# display_driver_shift_reg.net
KiCad netlist of a schematic drawn in EAGLE
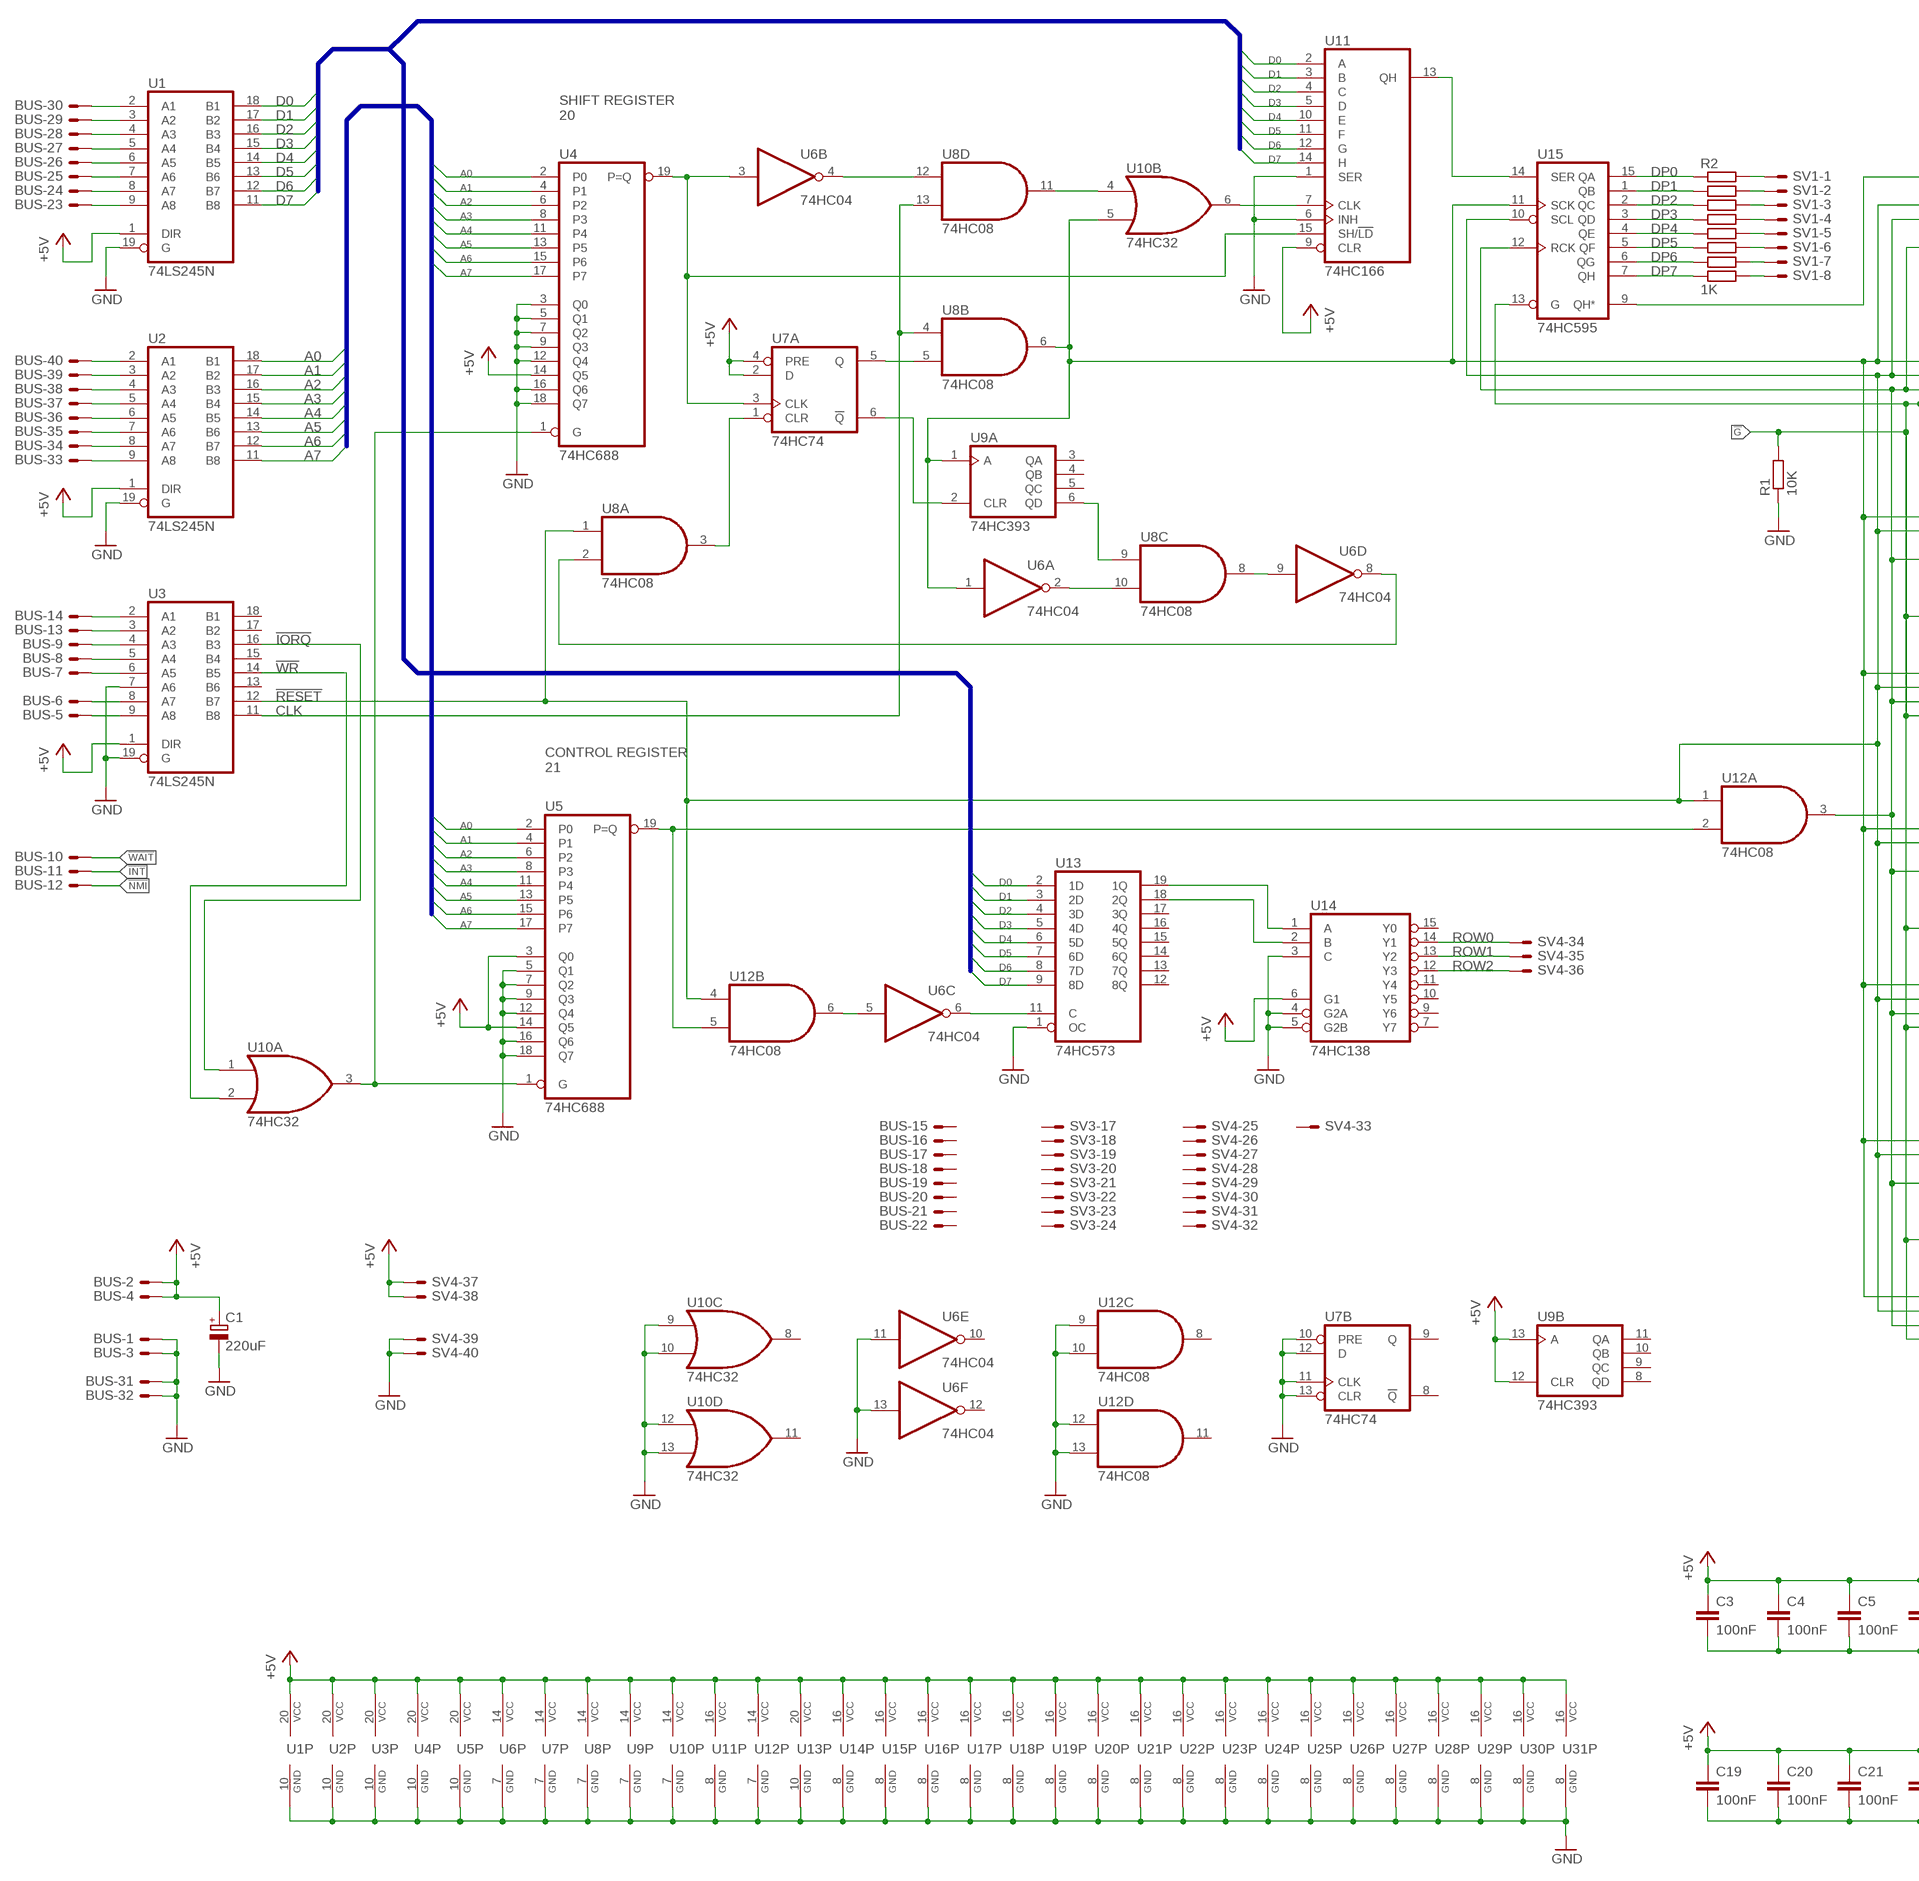
[diagram p0: schematic, sheet 1, part 1 of 2]
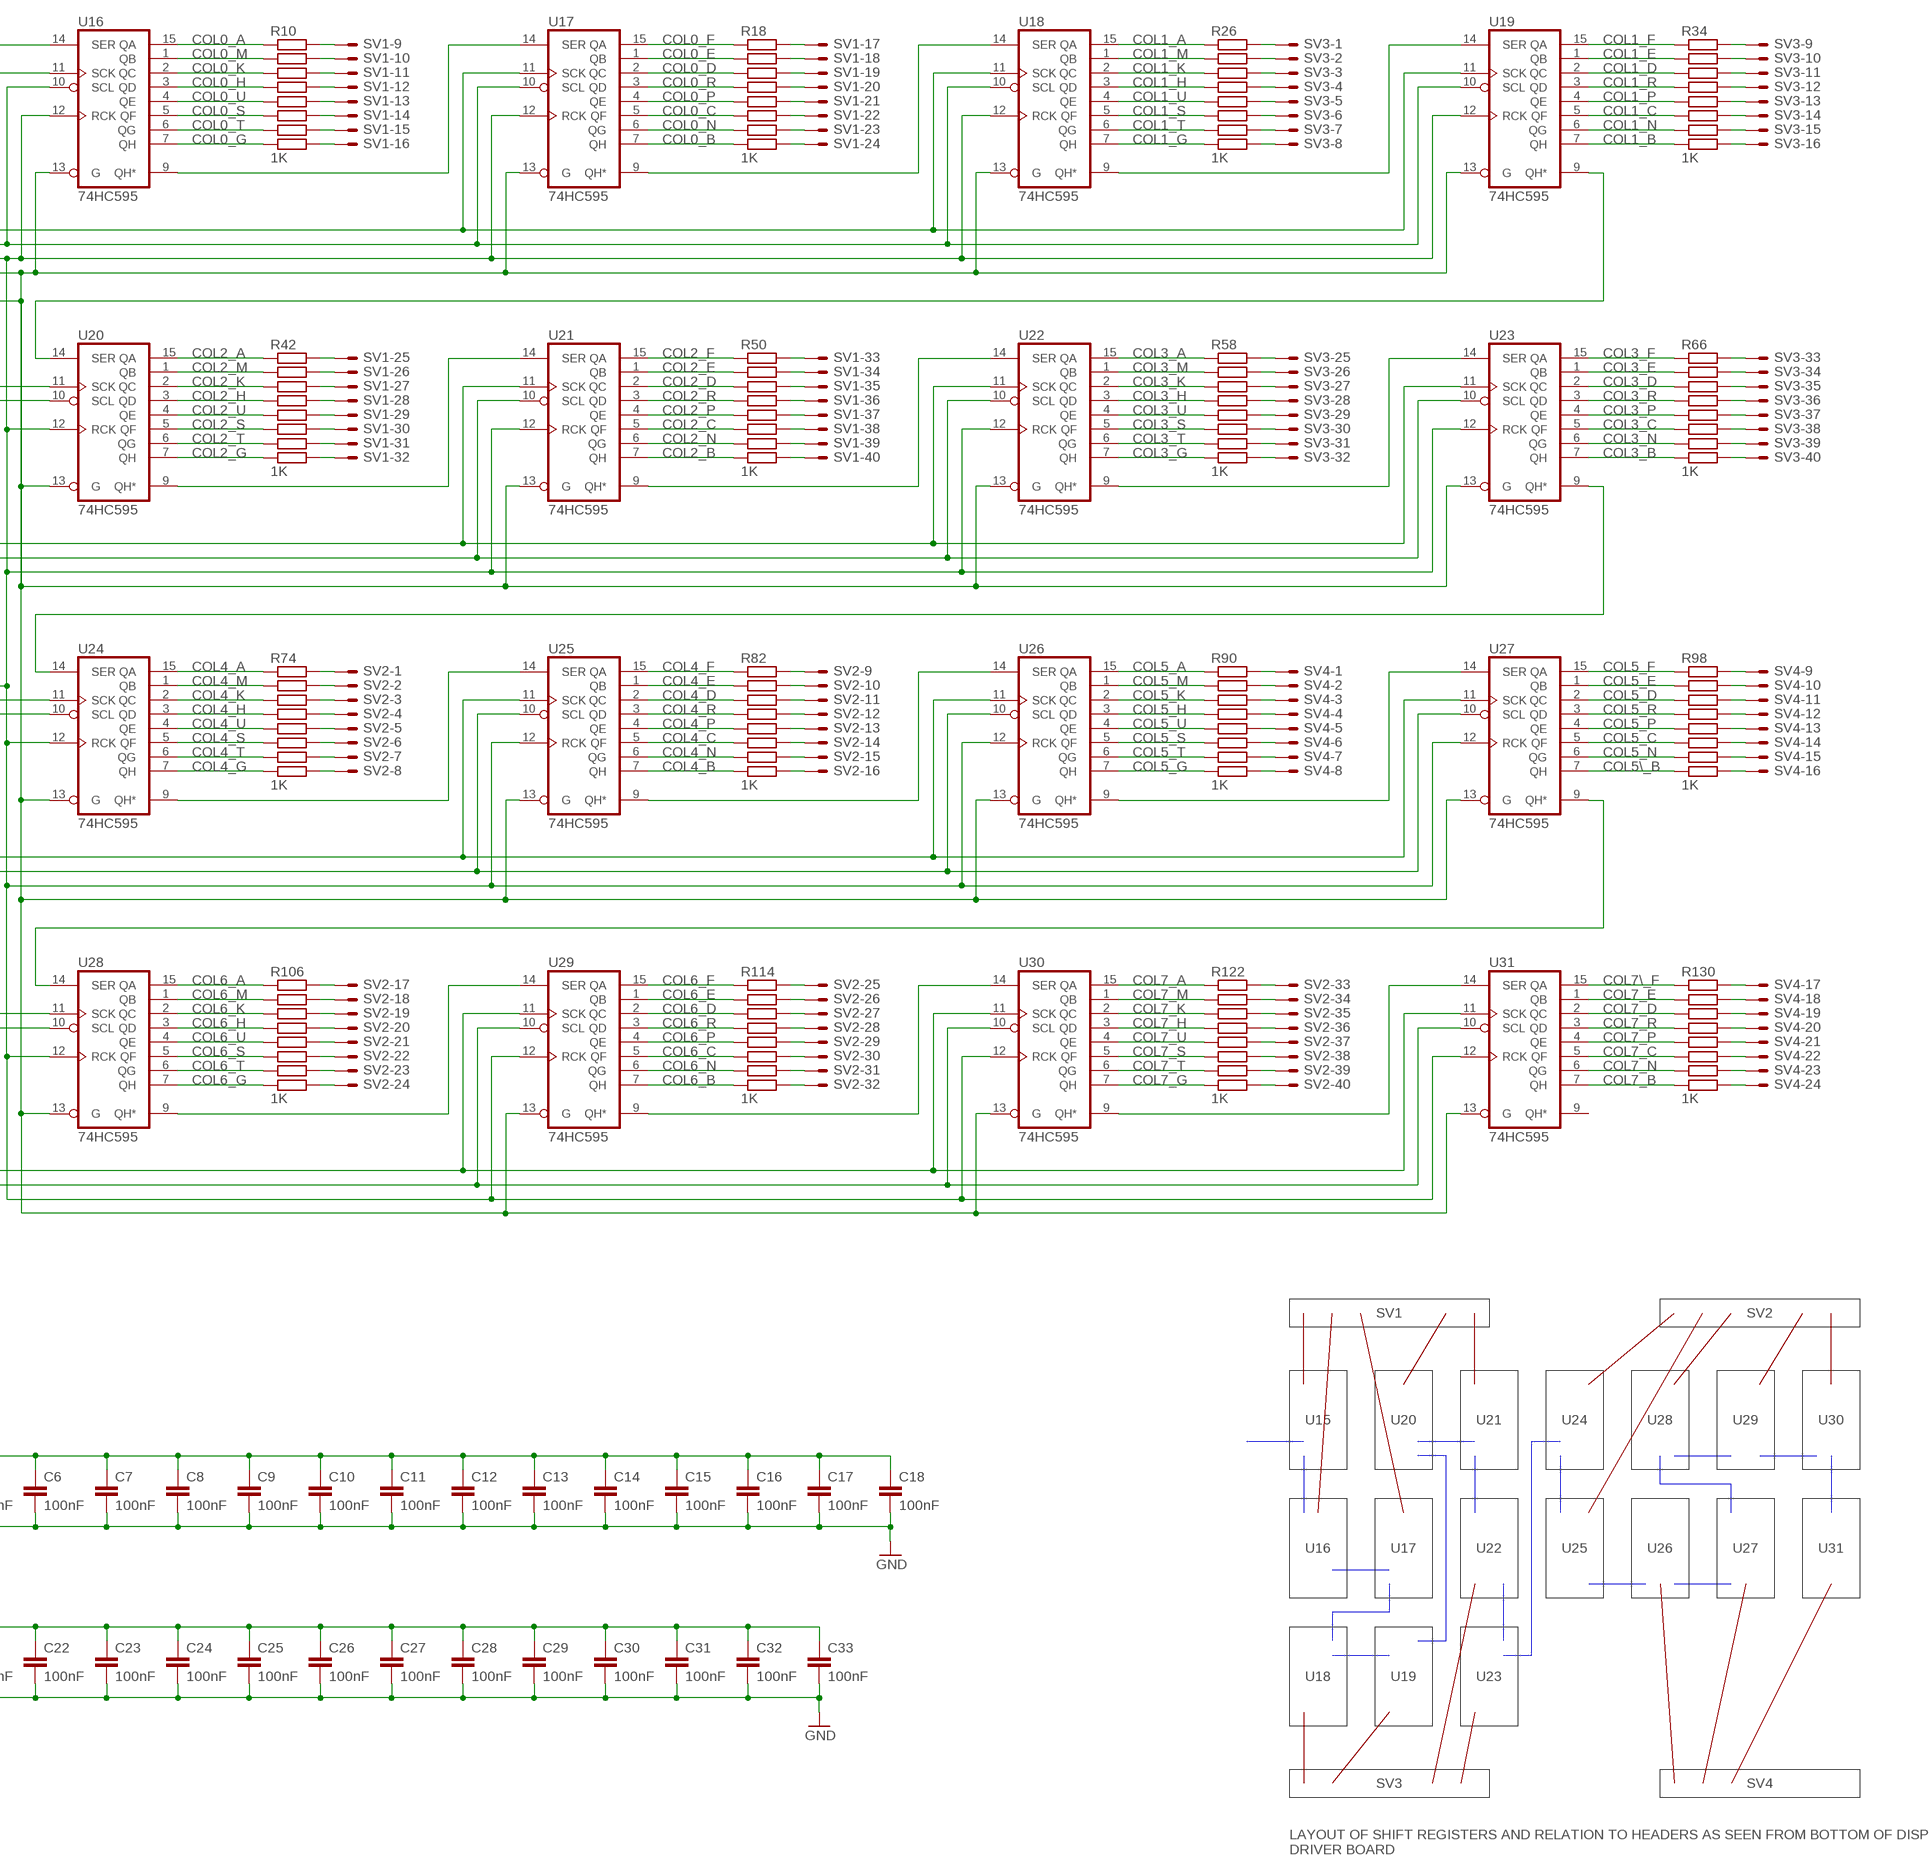
[diagram p1: schematic, sheet 1, part 2 of 2]

(export (version "E")
  (design (tool "Eeschema 10.0.6"))
  (components
    (comp (ref "BUS")
      (value "ML40E")
      (footprint "eagle-import:ML40")
      (libsource (lib "eagle-import") (part "ML40E"))
    )
    (comp (ref "C1")
      (value "220uF")
      (footprint "eagle-import:E3,5-8")
      (libsource (lib "eagle-import") (part "CPOL-EUE3.5-8"))
    )
    (comp (ref "C3")
      (value "100nF")
      (footprint "eagle-import:C050-025X075")
      (libsource (lib "eagle-import") (part "C-EU050-025X075"))
    )
    (comp (ref "C4")
      (value "100nF")
      (footprint "eagle-import:C050-025X075")
      (libsource (lib "eagle-import") (part "C-EU050-025X075"))
    )
    (comp (ref "C5")
      (value "100nF")
      (footprint "eagle-import:C050-025X075")
      (libsource (lib "eagle-import") (part "C-EU050-025X075"))
    )
    (comp (ref "C6")
      (value "100nF")
      (footprint "eagle-import:C050-025X075")
      (libsource (lib "eagle-import") (part "C-EU050-025X075"))
    )
    (comp (ref "C7")
      (value "100nF")
      (footprint "eagle-import:C050-025X075")
      (libsource (lib "eagle-import") (part "C-EU050-025X075"))
    )
    (comp (ref "C8")
      (value "100nF")
      (footprint "eagle-import:C050-025X075")
      (libsource (lib "eagle-import") (part "C-EU050-025X075"))
    )
    (comp (ref "C9")
      (value "100nF")
      (footprint "eagle-import:C050-025X075")
      (libsource (lib "eagle-import") (part "C-EU050-025X075"))
    )
    (comp (ref "C10")
      (value "100nF")
      (footprint "eagle-import:C050-025X075")
      (libsource (lib "eagle-import") (part "C-EU050-025X075"))
    )
    (comp (ref "C11")
      (value "100nF")
      (footprint "eagle-import:C050-025X075")
      (libsource (lib "eagle-import") (part "C-EU050-025X075"))
    )
    (comp (ref "C12")
      (value "100nF")
      (footprint "eagle-import:C050-025X075")
      (libsource (lib "eagle-import") (part "C-EU050-025X075"))
    )
    (comp (ref "C13")
      (value "100nF")
      (footprint "eagle-import:C050-025X075")
      (libsource (lib "eagle-import") (part "C-EU050-025X075"))
    )
    (comp (ref "C14")
      (value "100nF")
      (footprint "eagle-import:C050-025X075")
      (libsource (lib "eagle-import") (part "C-EU050-025X075"))
    )
    (comp (ref "C15")
      (value "100nF")
      (footprint "eagle-import:C050-025X075")
      (libsource (lib "eagle-import") (part "C-EU050-025X075"))
    )
    (comp (ref "C16")
      (value "100nF")
      (footprint "eagle-import:C050-025X075")
      (libsource (lib "eagle-import") (part "C-EU050-025X075"))
    )
    (comp (ref "C17")
      (value "100nF")
      (footprint "eagle-import:C050-025X075")
      (libsource (lib "eagle-import") (part "C-EU050-025X075"))
    )
    (comp (ref "C18")
      (value "100nF")
      (footprint "eagle-import:C050-025X075")
      (libsource (lib "eagle-import") (part "C-EU050-025X075"))
    )
    (comp (ref "C19")
      (value "100nF")
      (footprint "eagle-import:C050-025X075")
      (libsource (lib "eagle-import") (part "C-EU050-025X075"))
    )
    (comp (ref "C20")
      (value "100nF")
      (footprint "eagle-import:C050-025X075")
      (libsource (lib "eagle-import") (part "C-EU050-025X075"))
    )
    (comp (ref "C21")
      (value "100nF")
      (footprint "eagle-import:C050-025X075")
      (libsource (lib "eagle-import") (part "C-EU050-025X075"))
    )
    (comp (ref "C22")
      (value "100nF")
      (footprint "eagle-import:C050-025X075")
      (libsource (lib "eagle-import") (part "C-EU050-025X075"))
    )
    (comp (ref "C23")
      (value "100nF")
      (footprint "eagle-import:C050-025X075")
      (libsource (lib "eagle-import") (part "C-EU050-025X075"))
    )
    (comp (ref "C24")
      (value "100nF")
      (footprint "eagle-import:C050-025X075")
      (libsource (lib "eagle-import") (part "C-EU050-025X075"))
    )
    (comp (ref "C25")
      (value "100nF")
      (footprint "eagle-import:C050-025X075")
      (libsource (lib "eagle-import") (part "C-EU050-025X075"))
    )
    (comp (ref "C26")
      (value "100nF")
      (footprint "eagle-import:C050-025X075")
      (libsource (lib "eagle-import") (part "C-EU050-025X075"))
    )
    (comp (ref "C27")
      (value "100nF")
      (footprint "eagle-import:C050-025X075")
      (libsource (lib "eagle-import") (part "C-EU050-025X075"))
    )
    (comp (ref "C28")
      (value "100nF")
      (footprint "eagle-import:C050-025X075")
      (libsource (lib "eagle-import") (part "C-EU050-025X075"))
    )
    (comp (ref "C29")
      (value "100nF")
      (footprint "eagle-import:C050-025X075")
      (libsource (lib "eagle-import") (part "C-EU050-025X075"))
    )
    (comp (ref "C30")
      (value "100nF")
      (footprint "eagle-import:C050-025X075")
      (libsource (lib "eagle-import") (part "C-EU050-025X075"))
    )
    (comp (ref "C31")
      (value "100nF")
      (footprint "eagle-import:C050-025X075")
      (libsource (lib "eagle-import") (part "C-EU050-025X075"))
    )
    (comp (ref "C32")
      (value "100nF")
      (footprint "eagle-import:C050-025X075")
      (libsource (lib "eagle-import") (part "C-EU050-025X075"))
    )
    (comp (ref "C33")
      (value "100nF")
      (footprint "eagle-import:C050-025X075")
      (libsource (lib "eagle-import") (part "C-EU050-025X075"))
    )
    (comp (ref "R1")
      (value "10K")
      (footprint "eagle-import:0207_10")
      (libsource (lib "eagle-import") (part "R-EU_0207/10"))
    )
    (comp (ref "R2")
      (value "1K")
      (footprint "eagle-import:0207_10")
      (libsource (lib "eagle-import") (part "R-EU_0207/10"))
    )
    (comp (ref "R3")
      (value "1K")
      (footprint "eagle-import:0207_10")
      (libsource (lib "eagle-import") (part "R-EU_0207/10"))
    )
    (comp (ref "R4")
      (value "1K")
      (footprint "eagle-import:0207_10")
      (libsource (lib "eagle-import") (part "R-EU_0207/10"))
    )
    (comp (ref "R5")
      (value "1K")
      (footprint "eagle-import:0207_10")
      (libsource (lib "eagle-import") (part "R-EU_0207/10"))
    )
    (comp (ref "R6")
      (value "1K")
      (footprint "eagle-import:0207_10")
      (libsource (lib "eagle-import") (part "R-EU_0207/10"))
    )
    (comp (ref "R7")
      (value "1K")
      (footprint "eagle-import:0207_10")
      (libsource (lib "eagle-import") (part "R-EU_0207/10"))
    )
    (comp (ref "R8")
      (value "1K")
      (footprint "eagle-import:0207_10")
      (libsource (lib "eagle-import") (part "R-EU_0207/10"))
    )
    (comp (ref "R9")
      (value "1K")
      (footprint "eagle-import:0207_10")
      (libsource (lib "eagle-import") (part "R-EU_0207/10"))
    )
    (comp (ref "R10")
      (value "1K")
      (footprint "eagle-import:0207_10")
      (libsource (lib "eagle-import") (part "R-EU_0207/10"))
    )
    (comp (ref "R11")
      (value "1K")
      (footprint "eagle-import:0207_10")
      (libsource (lib "eagle-import") (part "R-EU_0207/10"))
    )
    (comp (ref "R12")
      (value "1K")
      (footprint "eagle-import:0207_10")
      (libsource (lib "eagle-import") (part "R-EU_0207/10"))
    )
    (comp (ref "R13")
      (value "1K")
      (footprint "eagle-import:0207_10")
      (libsource (lib "eagle-import") (part "R-EU_0207/10"))
    )
    (comp (ref "R14")
      (value "1K")
      (footprint "eagle-import:0207_10")
      (libsource (lib "eagle-import") (part "R-EU_0207/10"))
    )
    (comp (ref "R15")
      (value "1K")
      (footprint "eagle-import:0207_10")
      (libsource (lib "eagle-import") (part "R-EU_0207/10"))
    )
    (comp (ref "R16")
      (value "1K")
      (footprint "eagle-import:0207_10")
      (libsource (lib "eagle-import") (part "R-EU_0207/10"))
    )
    (comp (ref "R17")
      (value "1K")
      (footprint "eagle-import:0207_10")
      (libsource (lib "eagle-import") (part "R-EU_0207/10"))
    )
    (comp (ref "R18")
      (value "1K")
      (footprint "eagle-import:0207_10")
      (libsource (lib "eagle-import") (part "R-EU_0207/10"))
    )
    (comp (ref "R19")
      (value "1K")
      (footprint "eagle-import:0207_10")
      (libsource (lib "eagle-import") (part "R-EU_0207/10"))
    )
    (comp (ref "R20")
      (value "1K")
      (footprint "eagle-import:0207_10")
      (libsource (lib "eagle-import") (part "R-EU_0207/10"))
    )
    (comp (ref "R21")
      (value "1K")
      (footprint "eagle-import:0207_10")
      (libsource (lib "eagle-import") (part "R-EU_0207/10"))
    )
    (comp (ref "R22")
      (value "1K")
      (footprint "eagle-import:0207_10")
      (libsource (lib "eagle-import") (part "R-EU_0207/10"))
    )
    (comp (ref "R23")
      (value "1K")
      (footprint "eagle-import:0207_10")
      (libsource (lib "eagle-import") (part "R-EU_0207/10"))
    )
    (comp (ref "R24")
      (value "1K")
      (footprint "eagle-import:0207_10")
      (libsource (lib "eagle-import") (part "R-EU_0207/10"))
    )
    (comp (ref "R25")
      (value "1K")
      (footprint "eagle-import:0207_10")
      (libsource (lib "eagle-import") (part "R-EU_0207/10"))
    )
    (comp (ref "R26")
      (value "1K")
      (footprint "eagle-import:0207_10")
      (libsource (lib "eagle-import") (part "R-EU_0207/10"))
    )
    (comp (ref "R27")
      (value "1K")
      (footprint "eagle-import:0207_10")
      (libsource (lib "eagle-import") (part "R-EU_0207/10"))
    )
    (comp (ref "R28")
      (value "1K")
      (footprint "eagle-import:0207_10")
      (libsource (lib "eagle-import") (part "R-EU_0207/10"))
    )
    (comp (ref "R29")
      (value "1K")
      (footprint "eagle-import:0207_10")
      (libsource (lib "eagle-import") (part "R-EU_0207/10"))
    )
    (comp (ref "R30")
      (value "1K")
      (footprint "eagle-import:0207_10")
      (libsource (lib "eagle-import") (part "R-EU_0207/10"))
    )
    (comp (ref "R31")
      (value "1K")
      (footprint "eagle-import:0207_10")
      (libsource (lib "eagle-import") (part "R-EU_0207/10"))
    )
    (comp (ref "R32")
      (value "1K")
      (footprint "eagle-import:0207_10")
      (libsource (lib "eagle-import") (part "R-EU_0207/10"))
    )
    (comp (ref "R33")
      (value "1K")
      (footprint "eagle-import:0207_10")
      (libsource (lib "eagle-import") (part "R-EU_0207/10"))
    )
    (comp (ref "R34")
      (value "1K")
      (footprint "eagle-import:0207_10")
      (libsource (lib "eagle-import") (part "R-EU_0207/10"))
    )
    (comp (ref "R35")
      (value "1K")
      (footprint "eagle-import:0207_10")
      (libsource (lib "eagle-import") (part "R-EU_0207/10"))
    )
    (comp (ref "R36")
      (value "1K")
      (footprint "eagle-import:0207_10")
      (libsource (lib "eagle-import") (part "R-EU_0207/10"))
    )
    (comp (ref "R37")
      (value "1K")
      (footprint "eagle-import:0207_10")
      (libsource (lib "eagle-import") (part "R-EU_0207/10"))
    )
    (comp (ref "R38")
      (value "1K")
      (footprint "eagle-import:0207_10")
      (libsource (lib "eagle-import") (part "R-EU_0207/10"))
    )
    (comp (ref "R39")
      (value "1K")
      (footprint "eagle-import:0207_10")
      (libsource (lib "eagle-import") (part "R-EU_0207/10"))
    )
    (comp (ref "R40")
      (value "1K")
      (footprint "eagle-import:0207_10")
      (libsource (lib "eagle-import") (part "R-EU_0207/10"))
    )
    (comp (ref "R41")
      (value "1K")
      (footprint "eagle-import:0207_10")
      (libsource (lib "eagle-import") (part "R-EU_0207/10"))
    )
    (comp (ref "R42")
      (value "1K")
      (footprint "eagle-import:0207_10")
      (libsource (lib "eagle-import") (part "R-EU_0207/10"))
    )
    (comp (ref "R43")
      (value "1K")
      (footprint "eagle-import:0207_10")
      (libsource (lib "eagle-import") (part "R-EU_0207/10"))
    )
    (comp (ref "R44")
      (value "1K")
      (footprint "eagle-import:0207_10")
      (libsource (lib "eagle-import") (part "R-EU_0207/10"))
    )
    (comp (ref "R45")
      (value "1K")
      (footprint "eagle-import:0207_10")
      (libsource (lib "eagle-import") (part "R-EU_0207/10"))
    )
    (comp (ref "R46")
      (value "1K")
      (footprint "eagle-import:0207_10")
      (libsource (lib "eagle-import") (part "R-EU_0207/10"))
    )
    (comp (ref "R47")
      (value "1K")
      (footprint "eagle-import:0207_10")
      (libsource (lib "eagle-import") (part "R-EU_0207/10"))
    )
    (comp (ref "R48")
      (value "1K")
      (footprint "eagle-import:0207_10")
      (libsource (lib "eagle-import") (part "R-EU_0207/10"))
    )
    (comp (ref "R49")
      (value "1K")
      (footprint "eagle-import:0207_10")
      (libsource (lib "eagle-import") (part "R-EU_0207/10"))
    )
    (comp (ref "R50")
      (value "1K")
      (footprint "eagle-import:0207_10")
      (libsource (lib "eagle-import") (part "R-EU_0207/10"))
    )
    (comp (ref "R51")
      (value "1K")
      (footprint "eagle-import:0207_10")
      (libsource (lib "eagle-import") (part "R-EU_0207/10"))
    )
    (comp (ref "R52")
      (value "1K")
      (footprint "eagle-import:0207_10")
      (libsource (lib "eagle-import") (part "R-EU_0207/10"))
    )
    (comp (ref "R53")
      (value "1K")
      (footprint "eagle-import:0207_10")
      (libsource (lib "eagle-import") (part "R-EU_0207/10"))
    )
    (comp (ref "R54")
      (value "1K")
      (footprint "eagle-import:0207_10")
      (libsource (lib "eagle-import") (part "R-EU_0207/10"))
    )
    (comp (ref "R55")
      (value "1K")
      (footprint "eagle-import:0207_10")
      (libsource (lib "eagle-import") (part "R-EU_0207/10"))
    )
    (comp (ref "R56")
      (value "1K")
      (footprint "eagle-import:0207_10")
      (libsource (lib "eagle-import") (part "R-EU_0207/10"))
    )
    (comp (ref "R57")
      (value "1K")
      (footprint "eagle-import:0207_10")
      (libsource (lib "eagle-import") (part "R-EU_0207/10"))
    )
    (comp (ref "R58")
      (value "1K")
      (footprint "eagle-import:0207_10")
      (libsource (lib "eagle-import") (part "R-EU_0207/10"))
    )
    (comp (ref "R59")
      (value "1K")
      (footprint "eagle-import:0207_10")
      (libsource (lib "eagle-import") (part "R-EU_0207/10"))
    )
    (comp (ref "R60")
      (value "1K")
      (footprint "eagle-import:0207_10")
      (libsource (lib "eagle-import") (part "R-EU_0207/10"))
    )
    (comp (ref "R61")
      (value "1K")
      (footprint "eagle-import:0207_10")
      (libsource (lib "eagle-import") (part "R-EU_0207/10"))
    )
    (comp (ref "R62")
      (value "1K")
      (footprint "eagle-import:0207_10")
      (libsource (lib "eagle-import") (part "R-EU_0207/10"))
    )
    (comp (ref "R63")
      (value "1K")
      (footprint "eagle-import:0207_10")
      (libsource (lib "eagle-import") (part "R-EU_0207/10"))
    )
    (comp (ref "R64")
      (value "1K")
      (footprint "eagle-import:0207_10")
      (libsource (lib "eagle-import") (part "R-EU_0207/10"))
    )
    (comp (ref "R65")
      (value "1K")
      (footprint "eagle-import:0207_10")
      (libsource (lib "eagle-import") (part "R-EU_0207/10"))
    )
    (comp (ref "R66")
      (value "1K")
      (footprint "eagle-import:0207_10")
      (libsource (lib "eagle-import") (part "R-EU_0207/10"))
    )
    (comp (ref "R67")
      (value "1K")
      (footprint "eagle-import:0207_10")
      (libsource (lib "eagle-import") (part "R-EU_0207/10"))
    )
    (comp (ref "R68")
      (value "1K")
      (footprint "eagle-import:0207_10")
      (libsource (lib "eagle-import") (part "R-EU_0207/10"))
    )
    (comp (ref "R69")
      (value "1K")
      (footprint "eagle-import:0207_10")
      (libsource (lib "eagle-import") (part "R-EU_0207/10"))
    )
    (comp (ref "R70")
      (value "1K")
      (footprint "eagle-import:0207_10")
      (libsource (lib "eagle-import") (part "R-EU_0207/10"))
    )
    (comp (ref "R71")
      (value "1K")
      (footprint "eagle-import:0207_10")
      (libsource (lib "eagle-import") (part "R-EU_0207/10"))
    )
    (comp (ref "R72")
      (value "1K")
      (footprint "eagle-import:0207_10")
      (libsource (lib "eagle-import") (part "R-EU_0207/10"))
    )
    (comp (ref "R73")
      (value "1K")
      (footprint "eagle-import:0207_10")
      (libsource (lib "eagle-import") (part "R-EU_0207/10"))
    )
    (comp (ref "R74")
      (value "1K")
      (footprint "eagle-import:0207_10")
      (libsource (lib "eagle-import") (part "R-EU_0207/10"))
    )
    (comp (ref "R75")
      (value "1K")
      (footprint "eagle-import:0207_10")
      (libsource (lib "eagle-import") (part "R-EU_0207/10"))
    )
    (comp (ref "R76")
      (value "1K")
      (footprint "eagle-import:0207_10")
      (libsource (lib "eagle-import") (part "R-EU_0207/10"))
    )
    (comp (ref "R77")
      (value "1K")
      (footprint "eagle-import:0207_10")
      (libsource (lib "eagle-import") (part "R-EU_0207/10"))
    )
    (comp (ref "R78")
      (value "1K")
      (footprint "eagle-import:0207_10")
      (libsource (lib "eagle-import") (part "R-EU_0207/10"))
    )
    (comp (ref "R79")
      (value "1K")
      (footprint "eagle-import:0207_10")
      (libsource (lib "eagle-import") (part "R-EU_0207/10"))
    )
    (comp (ref "R80")
      (value "1K")
      (footprint "eagle-import:0207_10")
      (libsource (lib "eagle-import") (part "R-EU_0207/10"))
    )
    (comp (ref "R81")
      (value "1K")
      (footprint "eagle-import:0207_10")
      (libsource (lib "eagle-import") (part "R-EU_0207/10"))
    )
    (comp (ref "R82")
      (value "1K")
      (footprint "eagle-import:0207_10")
      (libsource (lib "eagle-import") (part "R-EU_0207/10"))
    )
    (comp (ref "R83")
      (value "1K")
      (footprint "eagle-import:0207_10")
      (libsource (lib "eagle-import") (part "R-EU_0207/10"))
    )
    (comp (ref "R84")
      (value "1K")
      (footprint "eagle-import:0207_10")
      (libsource (lib "eagle-import") (part "R-EU_0207/10"))
    )
    (comp (ref "R85")
      (value "1K")
      (footprint "eagle-import:0207_10")
      (libsource (lib "eagle-import") (part "R-EU_0207/10"))
    )
    (comp (ref "R86")
      (value "1K")
      (footprint "eagle-import:0207_10")
      (libsource (lib "eagle-import") (part "R-EU_0207/10"))
    )
    (comp (ref "R87")
      (value "1K")
      (footprint "eagle-import:0207_10")
      (libsource (lib "eagle-import") (part "R-EU_0207/10"))
    )
    (comp (ref "R88")
      (value "1K")
      (footprint "eagle-import:0207_10")
      (libsource (lib "eagle-import") (part "R-EU_0207/10"))
    )
    (comp (ref "R89")
      (value "1K")
      (footprint "eagle-import:0207_10")
      (libsource (lib "eagle-import") (part "R-EU_0207/10"))
    )
    (comp (ref "R90")
      (value "1K")
      (footprint "eagle-import:0207_10")
      (libsource (lib "eagle-import") (part "R-EU_0207/10"))
    )
    (comp (ref "R91")
      (value "1K")
      (footprint "eagle-import:0207_10")
      (libsource (lib "eagle-import") (part "R-EU_0207/10"))
    )
    (comp (ref "R92")
      (value "1K")
      (footprint "eagle-import:0207_10")
      (libsource (lib "eagle-import") (part "R-EU_0207/10"))
    )
    (comp (ref "R93")
      (value "1K")
      (footprint "eagle-import:0207_10")
      (libsource (lib "eagle-import") (part "R-EU_0207/10"))
    )
    (comp (ref "R94")
      (value "1K")
      (footprint "eagle-import:0207_10")
      (libsource (lib "eagle-import") (part "R-EU_0207/10"))
    )
    (comp (ref "R95")
      (value "1K")
      (footprint "eagle-import:0207_10")
      (libsource (lib "eagle-import") (part "R-EU_0207/10"))
    )
    (comp (ref "R96")
      (value "1K")
      (footprint "eagle-import:0207_10")
      (libsource (lib "eagle-import") (part "R-EU_0207/10"))
    )
    (comp (ref "R97")
      (value "1K")
      (footprint "eagle-import:0207_10")
      (libsource (lib "eagle-import") (part "R-EU_0207/10"))
    )
    (comp (ref "R98")
      (value "1K")
      (footprint "eagle-import:0207_10")
      (libsource (lib "eagle-import") (part "R-EU_0207/10"))
    )
    (comp (ref "R99")
      (value "1K")
      (footprint "eagle-import:0207_10")
      (libsource (lib "eagle-import") (part "R-EU_0207/10"))
    )
    (comp (ref "R100")
      (value "1K")
      (footprint "eagle-import:0207_10")
      (libsource (lib "eagle-import") (part "R-EU_0207/10"))
    )
    (comp (ref "R101")
      (value "1K")
      (footprint "eagle-import:0207_10")
      (libsource (lib "eagle-import") (part "R-EU_0207/10"))
    )
    (comp (ref "R102")
      (value "1K")
      (footprint "eagle-import:0207_10")
      (libsource (lib "eagle-import") (part "R-EU_0207/10"))
    )
    (comp (ref "R103")
      (value "1K")
      (footprint "eagle-import:0207_10")
      (libsource (lib "eagle-import") (part "R-EU_0207/10"))
    )
    (comp (ref "R104")
      (value "1K")
      (footprint "eagle-import:0207_10")
      (libsource (lib "eagle-import") (part "R-EU_0207/10"))
    )
    (comp (ref "R105")
      (value "1K")
      (footprint "eagle-import:0207_10")
      (libsource (lib "eagle-import") (part "R-EU_0207/10"))
    )
    (comp (ref "R106")
      (value "1K")
      (footprint "eagle-import:0207_10")
      (libsource (lib "eagle-import") (part "R-EU_0207/10"))
    )
    (comp (ref "R107")
      (value "1K")
      (footprint "eagle-import:0207_10")
      (libsource (lib "eagle-import") (part "R-EU_0207/10"))
    )
    (comp (ref "R108")
      (value "1K")
      (footprint "eagle-import:0207_10")
      (libsource (lib "eagle-import") (part "R-EU_0207/10"))
    )
    (comp (ref "R109")
      (value "1K")
      (footprint "eagle-import:0207_10")
      (libsource (lib "eagle-import") (part "R-EU_0207/10"))
    )
    (comp (ref "R110")
      (value "1K")
      (footprint "eagle-import:0207_10")
      (libsource (lib "eagle-import") (part "R-EU_0207/10"))
    )
    (comp (ref "R111")
      (value "1K")
      (footprint "eagle-import:0207_10")
      (libsource (lib "eagle-import") (part "R-EU_0207/10"))
    )
    (comp (ref "R112")
      (value "1K")
      (footprint "eagle-import:0207_10")
      (libsource (lib "eagle-import") (part "R-EU_0207/10"))
    )
    (comp (ref "R113")
      (value "1K")
      (footprint "eagle-import:0207_10")
      (libsource (lib "eagle-import") (part "R-EU_0207/10"))
    )
    (comp (ref "R114")
      (value "1K")
      (footprint "eagle-import:0207_10")
      (libsource (lib "eagle-import") (part "R-EU_0207/10"))
    )
    (comp (ref "R115")
      (value "1K")
      (footprint "eagle-import:0207_10")
      (libsource (lib "eagle-import") (part "R-EU_0207/10"))
    )
    (comp (ref "R116")
      (value "1K")
      (footprint "eagle-import:0207_10")
      (libsource (lib "eagle-import") (part "R-EU_0207/10"))
    )
    (comp (ref "R117")
      (value "1K")
      (footprint "eagle-import:0207_10")
      (libsource (lib "eagle-import") (part "R-EU_0207/10"))
    )
    (comp (ref "R118")
      (value "1K")
      (footprint "eagle-import:0207_10")
      (libsource (lib "eagle-import") (part "R-EU_0207/10"))
    )
    (comp (ref "R119")
      (value "1K")
      (footprint "eagle-import:0207_10")
      (libsource (lib "eagle-import") (part "R-EU_0207/10"))
    )
    (comp (ref "R120")
      (value "1K")
      (footprint "eagle-import:0207_10")
      (libsource (lib "eagle-import") (part "R-EU_0207/10"))
    )
    (comp (ref "R121")
      (value "1K")
      (footprint "eagle-import:0207_10")
      (libsource (lib "eagle-import") (part "R-EU_0207/10"))
    )
    (comp (ref "R122")
      (value "1K")
      (footprint "eagle-import:0207_10")
      (libsource (lib "eagle-import") (part "R-EU_0207/10"))
    )
    (comp (ref "R123")
      (value "1K")
      (footprint "eagle-import:0207_10")
      (libsource (lib "eagle-import") (part "R-EU_0207/10"))
    )
    (comp (ref "R124")
      (value "1K")
      (footprint "eagle-import:0207_10")
      (libsource (lib "eagle-import") (part "R-EU_0207/10"))
    )
    (comp (ref "R125")
      (value "1K")
      (footprint "eagle-import:0207_10")
      (libsource (lib "eagle-import") (part "R-EU_0207/10"))
    )
    (comp (ref "R126")
      (value "1K")
      (footprint "eagle-import:0207_10")
      (libsource (lib "eagle-import") (part "R-EU_0207/10"))
    )
    (comp (ref "R127")
      (value "1K")
      (footprint "eagle-import:0207_10")
      (libsource (lib "eagle-import") (part "R-EU_0207/10"))
    )
    (comp (ref "R128")
      (value "1K")
      (footprint "eagle-import:0207_10")
      (libsource (lib "eagle-import") (part "R-EU_0207/10"))
    )
    (comp (ref "R129")
      (value "1K")
      (footprint "eagle-import:0207_10")
      (libsource (lib "eagle-import") (part "R-EU_0207/10"))
    )
    (comp (ref "R130")
      (value "1K")
      (footprint "eagle-import:0207_10")
      (libsource (lib "eagle-import") (part "R-EU_0207/10"))
    )
    (comp (ref "R131")
      (value "1K")
      (footprint "eagle-import:0207_10")
      (libsource (lib "eagle-import") (part "R-EU_0207/10"))
    )
    (comp (ref "R132")
      (value "1K")
      (footprint "eagle-import:0207_10")
      (libsource (lib "eagle-import") (part "R-EU_0207/10"))
    )
    (comp (ref "R133")
      (value "1K")
      (footprint "eagle-import:0207_10")
      (libsource (lib "eagle-import") (part "R-EU_0207/10"))
    )
    (comp (ref "R134")
      (value "1K")
      (footprint "eagle-import:0207_10")
      (libsource (lib "eagle-import") (part "R-EU_0207/10"))
    )
    (comp (ref "R135")
      (value "1K")
      (footprint "eagle-import:0207_10")
      (libsource (lib "eagle-import") (part "R-EU_0207/10"))
    )
    (comp (ref "R136")
      (value "1K")
      (footprint "eagle-import:0207_10")
      (libsource (lib "eagle-import") (part "R-EU_0207/10"))
    )
    (comp (ref "R137")
      (value "1K")
      (footprint "eagle-import:0207_10")
      (libsource (lib "eagle-import") (part "R-EU_0207/10"))
    )
    (comp (ref "SV1")
      (value "ML40E")
      (footprint "eagle-import:ML40")
      (libsource (lib "eagle-import") (part "ML40E"))
    )
    (comp (ref "SV2")
      (value "ML40E")
      (footprint "eagle-import:ML40")
      (libsource (lib "eagle-import") (part "ML40E"))
    )
    (comp (ref "SV3")
      (value "ML40E")
      (footprint "eagle-import:ML40")
      (libsource (lib "eagle-import") (part "ML40E"))
    )
    (comp (ref "SV4")
      (value "ML40E")
      (footprint "eagle-import:ML40")
      (libsource (lib "eagle-import") (part "ML40E"))
    )
    (comp (ref "U1")
      (value "74LS245N")
      (footprint "eagle-import:DIL20")
      (libsource (lib "eagle-import") (part "74245NLS"))
    )
    (comp (ref "U2")
      (value "74LS245N")
      (footprint "eagle-import:DIL20")
      (libsource (lib "eagle-import") (part "74245NLS"))
    )
    (comp (ref "U3")
      (value "74LS245N")
      (footprint "eagle-import:DIL20")
      (libsource (lib "eagle-import") (part "74245NLS"))
    )
    (comp (ref "U4")
      (value "74HC688")
      (footprint "eagle-import:DIL20")
      (libsource (lib "eagle-import") (part "74688NLS"))
    )
    (comp (ref "U5")
      (value "74HC688")
      (footprint "eagle-import:DIL20")
      (libsource (lib "eagle-import") (part "74688NLS"))
    )
    (comp (ref "U6")
      (value "74HC04")
      (footprint "eagle-import:DIL14")
      (libsource (lib "eagle-import") (part "7404NLS"))
    )
    (comp (ref "U7")
      (value "74HC74")
      (footprint "eagle-import:DIL14")
      (libsource (lib "eagle-import") (part "7474NLS"))
    )
    (comp (ref "U8")
      (value "74HC08")
      (footprint "eagle-import:DIL14")
      (libsource (lib "eagle-import") (part "7408NLS"))
    )
    (comp (ref "U9")
      (value "74HC393")
      (footprint "eagle-import:DIL14")
      (libsource (lib "eagle-import") (part "74393NLS"))
    )
    (comp (ref "U10")
      (value "74HC32")
      (footprint "eagle-import:DIL14")
      (libsource (lib "eagle-import") (part "7432NLS"))
    )
    (comp (ref "U11")
      (value "74HC166")
      (footprint "eagle-import:DIL16")
      (libsource (lib "eagle-import") (part "74166NLS"))
    )
    (comp (ref "U12")
      (value "74HC08")
      (footprint "eagle-import:DIL14")
      (fields (field (name "SPICEPREFIX") "J"))
      (libsource (lib "eagle-import") (part "7408NLS"))
    )
    (comp (ref "U13")
      (value "74HC573")
      (footprint "eagle-import:DIL20")
      (libsource (lib "eagle-import") (part "74573NHC"))
    )
    (comp (ref "U14")
      (value "74HC138")
      (footprint "eagle-import:DIL16")
      (libsource (lib "eagle-import") (part "74138NLS"))
    )
    (comp (ref "U15")
      (value "74HC595")
      (footprint "eagle-import:DIL16")
      (libsource (lib "eagle-import") (part "74595NLS"))
    )
    (comp (ref "U16")
      (value "74HC595")
      (footprint "eagle-import:DIL16")
      (libsource (lib "eagle-import") (part "74595NLS"))
    )
    (comp (ref "U17")
      (value "74HC595")
      (footprint "eagle-import:DIL16")
      (libsource (lib "eagle-import") (part "74595NLS"))
    )
    (comp (ref "U18")
      (value "74HC595")
      (footprint "eagle-import:DIL16")
      (libsource (lib "eagle-import") (part "74595NLS"))
    )
    (comp (ref "U19")
      (value "74HC595")
      (footprint "eagle-import:DIL16")
      (libsource (lib "eagle-import") (part "74595NLS"))
    )
    (comp (ref "U20")
      (value "74HC595")
      (footprint "eagle-import:DIL16")
      (libsource (lib "eagle-import") (part "74595NLS"))
    )
    (comp (ref "U21")
      (value "74HC595")
      (footprint "eagle-import:DIL16")
      (libsource (lib "eagle-import") (part "74595NLS"))
    )
    (comp (ref "U22")
      (value "74HC595")
      (footprint "eagle-import:DIL16")
      (libsource (lib "eagle-import") (part "74595NLS"))
    )
    (comp (ref "U23")
      (value "74HC595")
      (footprint "eagle-import:DIL16")
      (libsource (lib "eagle-import") (part "74595NLS"))
    )
    (comp (ref "U24")
      (value "74HC595")
      (footprint "eagle-import:DIL16")
      (libsource (lib "eagle-import") (part "74595NLS"))
    )
    (comp (ref "U25")
      (value "74HC595")
      (footprint "eagle-import:DIL16")
      (libsource (lib "eagle-import") (part "74595NLS"))
    )
    (comp (ref "U26")
      (value "74HC595")
      (footprint "eagle-import:DIL16")
      (libsource (lib "eagle-import") (part "74595NLS"))
    )
    (comp (ref "U27")
      (value "74HC595")
      (footprint "eagle-import:DIL16")
      (libsource (lib "eagle-import") (part "74595NLS"))
    )
    (comp (ref "U28")
      (value "74HC595")
      (footprint "eagle-import:DIL16")
      (libsource (lib "eagle-import") (part "74595NLS"))
    )
    (comp (ref "U29")
      (value "74HC595")
      (footprint "eagle-import:DIL16")
      (libsource (lib "eagle-import") (part "74595NLS"))
    )
    (comp (ref "U30")
      (value "74HC595")
      (footprint "eagle-import:DIL16")
      (libsource (lib "eagle-import") (part "74595NLS"))
    )
    (comp (ref "U31")
      (value "74HC595")
      (footprint "eagle-import:DIL16")
      (libsource (lib "eagle-import") (part "74595NLS"))
    )
  )
  (nets
    (net (code "1") (name "+5V") (class "Default")
      (node (ref "BUS") (pin "2") (pinfunction "S_2") (pintype "passive"))
      (node (ref "BUS") (pin "4") (pinfunction "S_4") (pintype "passive"))
      (node (ref "C1") (pin "+") (pinfunction "+_+") (pintype "passive"))
      (node (ref "C10") (pin "1") (pinfunction "1_1") (pintype "passive"))
      (node (ref "C11") (pin "1") (pinfunction "1_1") (pintype "passive"))
      (node (ref "C12") (pin "1") (pinfunction "1_1") (pintype "passive"))
      (node (ref "C13") (pin "1") (pinfunction "1_1") (pintype "passive"))
      (node (ref "C14") (pin "1") (pinfunction "1_1") (pintype "passive"))
      (node (ref "C15") (pin "1") (pinfunction "1_1") (pintype "passive"))
      (node (ref "C16") (pin "1") (pinfunction "1_1") (pintype "passive"))
      (node (ref "C17") (pin "1") (pinfunction "1_1") (pintype "passive"))
      (node (ref "C18") (pin "1") (pinfunction "1_1") (pintype "passive"))
      (node (ref "C19") (pin "1") (pinfunction "1_1") (pintype "passive"))
      (node (ref "C20") (pin "1") (pinfunction "1_1") (pintype "passive"))
      (node (ref "C21") (pin "1") (pinfunction "1_1") (pintype "passive"))
      (node (ref "C22") (pin "1") (pinfunction "1_1") (pintype "passive"))
      (node (ref "C23") (pin "1") (pinfunction "1_1") (pintype "passive"))
      (node (ref "C24") (pin "1") (pinfunction "1_1") (pintype "passive"))
      (node (ref "C25") (pin "1") (pinfunction "1_1") (pintype "passive"))
      (node (ref "C26") (pin "1") (pinfunction "1_1") (pintype "passive"))
      (node (ref "C27") (pin "1") (pinfunction "1_1") (pintype "passive"))
      (node (ref "C28") (pin "1") (pinfunction "1_1") (pintype "passive"))
      (node (ref "C29") (pin "1") (pinfunction "1_1") (pintype "passive"))
      (node (ref "C3") (pin "1") (pinfunction "1_1") (pintype "passive"))
      (node (ref "C30") (pin "1") (pinfunction "1_1") (pintype "passive"))
      (node (ref "C31") (pin "1") (pinfunction "1_1") (pintype "passive"))
      (node (ref "C32") (pin "1") (pinfunction "1_1") (pintype "passive"))
      (node (ref "C33") (pin "1") (pinfunction "1_1") (pintype "passive"))
      (node (ref "C4") (pin "1") (pinfunction "1_1") (pintype "passive"))
      (node (ref "C5") (pin "1") (pinfunction "1_1") (pintype "passive"))
      (node (ref "C6") (pin "1") (pinfunction "1_1") (pintype "passive"))
      (node (ref "C7") (pin "1") (pinfunction "1_1") (pintype "passive"))
      (node (ref "C8") (pin "1") (pinfunction "1_1") (pintype "passive"))
      (node (ref "C9") (pin "1") (pinfunction "1_1") (pintype "passive"))
      (node (ref "SV4") (pin "37") (pinfunction "S_37") (pintype "passive"))
      (node (ref "SV4") (pin "38") (pinfunction "S_38") (pintype "passive"))
      (node (ref "U1") (pin "1") (pinfunction "DIR_1") (pintype "input"))
      (node (ref "U1") (pin "20") (pinfunction "VCC_20") (pintype "power_in"))
      (node (ref "U10") (pin "14") (pinfunction "VCC_14") (pintype "power_in"))
      (node (ref "U11") (pin "16") (pinfunction "VCC_16") (pintype "power_in"))
      (node (ref "U11") (pin "9") (pinfunction "CLR_9") (pintype "input"))
      (node (ref "U12") (pin "14") (pinfunction "VCC_14") (pintype "power_in"))
      (node (ref "U13") (pin "20") (pinfunction "VCC_20") (pintype "power_in"))
      (node (ref "U14") (pin "16") (pinfunction "VCC_16") (pintype "power_in"))
      (node (ref "U14") (pin "6") (pinfunction "G1_6") (pintype "input"))
      (node (ref "U15") (pin "16") (pinfunction "VCC_16") (pintype "power_in"))
      (node (ref "U16") (pin "16") (pinfunction "VCC_16") (pintype "power_in"))
      (node (ref "U17") (pin "16") (pinfunction "VCC_16") (pintype "power_in"))
      (node (ref "U18") (pin "16") (pinfunction "VCC_16") (pintype "power_in"))
      (node (ref "U19") (pin "16") (pinfunction "VCC_16") (pintype "power_in"))
      (node (ref "U2") (pin "1") (pinfunction "DIR_1") (pintype "input"))
      (node (ref "U2") (pin "20") (pinfunction "VCC_20") (pintype "power_in"))
      (node (ref "U20") (pin "16") (pinfunction "VCC_16") (pintype "power_in"))
      (node (ref "U21") (pin "16") (pinfunction "VCC_16") (pintype "power_in"))
      (node (ref "U22") (pin "16") (pinfunction "VCC_16") (pintype "power_in"))
      (node (ref "U23") (pin "16") (pinfunction "VCC_16") (pintype "power_in"))
      (node (ref "U24") (pin "16") (pinfunction "VCC_16") (pintype "power_in"))
      (node (ref "U25") (pin "16") (pinfunction "VCC_16") (pintype "power_in"))
      (node (ref "U26") (pin "16") (pinfunction "VCC_16") (pintype "power_in"))
      (node (ref "U27") (pin "16") (pinfunction "VCC_16") (pintype "power_in"))
      (node (ref "U28") (pin "16") (pinfunction "VCC_16") (pintype "power_in"))
      (node (ref "U29") (pin "16") (pinfunction "VCC_16") (pintype "power_in"))
      (node (ref "U3") (pin "1") (pinfunction "DIR_1") (pintype "input"))
      (node (ref "U3") (pin "20") (pinfunction "VCC_20") (pintype "power_in"))
      (node (ref "U30") (pin "16") (pinfunction "VCC_16") (pintype "power_in"))
      (node (ref "U31") (pin "16") (pinfunction "VCC_16") (pintype "power_in"))
      (node (ref "U4") (pin "14") (pinfunction "Q5_14") (pintype "input"))
      (node (ref "U4") (pin "20") (pinfunction "VCC_20") (pintype "power_in"))
      (node (ref "U5") (pin "14") (pinfunction "Q5_14") (pintype "input"))
      (node (ref "U5") (pin "20") (pinfunction "VCC_20") (pintype "power_in"))
      (node (ref "U5") (pin "3") (pinfunction "Q0_3") (pintype "input"))
      (node (ref "U6") (pin "14") (pinfunction "VCC_14") (pintype "power_in"))
      (node (ref "U7") (pin "14") (pinfunction "VCC_14") (pintype "power_in"))
      (node (ref "U7") (pin "2") (pinfunction "D_2") (pintype "input"))
      (node (ref "U7") (pin "4") (pinfunction "PRE_4") (pintype "input"))
      (node (ref "U8") (pin "14") (pinfunction "VCC_14") (pintype "power_in"))
      (node (ref "U9") (pin "12") (pinfunction "CLR_12") (pintype "input"))
      (node (ref "U9") (pin "13") (pinfunction "A_13") (pintype "input"))
      (node (ref "U9") (pin "14") (pinfunction "VCC_14") (pintype "power_in"))
    )
    (net (code "2") (name "/A0") (class "Default")
      (node (ref "U2") (pin "18") (pinfunction "B1_18") (pintype "bidirectional"))
      (node (ref "U4") (pin "2") (pinfunction "P0_2") (pintype "input"))
      (node (ref "U5") (pin "2") (pinfunction "P0_2") (pintype "input"))
    )
    (net (code "3") (name "/A1") (class "Default")
      (node (ref "U2") (pin "17") (pinfunction "B2_17") (pintype "bidirectional"))
      (node (ref "U4") (pin "4") (pinfunction "P1_4") (pintype "input"))
      (node (ref "U5") (pin "4") (pinfunction "P1_4") (pintype "input"))
    )
    (net (code "4") (name "/A2") (class "Default")
      (node (ref "U2") (pin "16") (pinfunction "B3_16") (pintype "bidirectional"))
      (node (ref "U4") (pin "6") (pinfunction "P2_6") (pintype "input"))
      (node (ref "U5") (pin "6") (pinfunction "P2_6") (pintype "input"))
    )
    (net (code "5") (name "/A3") (class "Default")
      (node (ref "U2") (pin "15") (pinfunction "B4_15") (pintype "bidirectional"))
      (node (ref "U4") (pin "8") (pinfunction "P3_8") (pintype "input"))
      (node (ref "U5") (pin "8") (pinfunction "P3_8") (pintype "input"))
    )
    (net (code "6") (name "/A4") (class "Default")
      (node (ref "U2") (pin "14") (pinfunction "B5_14") (pintype "bidirectional"))
      (node (ref "U4") (pin "11") (pinfunction "P4_11") (pintype "input"))
      (node (ref "U5") (pin "11") (pinfunction "P4_11") (pintype "input"))
    )
    (net (code "7") (name "/A5") (class "Default")
      (node (ref "U2") (pin "13") (pinfunction "B6_13") (pintype "bidirectional"))
      (node (ref "U4") (pin "13") (pinfunction "P5_13") (pintype "input"))
      (node (ref "U5") (pin "13") (pinfunction "P5_13") (pintype "input"))
    )
    (net (code "8") (name "/A6") (class "Default")
      (node (ref "U2") (pin "12") (pinfunction "B7_12") (pintype "bidirectional"))
      (node (ref "U4") (pin "15") (pinfunction "P6_15") (pintype "input"))
      (node (ref "U5") (pin "15") (pinfunction "P6_15") (pintype "input"))
    )
    (net (code "9") (name "/A7") (class "Default")
      (node (ref "U2") (pin "11") (pinfunction "B8_11") (pintype "bidirectional"))
      (node (ref "U4") (pin "17") (pinfunction "P7_17") (pintype "input"))
      (node (ref "U5") (pin "17") (pinfunction "P7_17") (pintype "input"))
    )
    (net (code "10") (name "/CLK") (class "Default")
      (node (ref "U3") (pin "11") (pinfunction "B8_11") (pintype "bidirectional"))
      (node (ref "U8") (pin "13") (pinfunction "I1_13") (pintype "input"))
      (node (ref "U8") (pin "4") (pinfunction "I0_4") (pintype "input"))
    )
    (net (code "11") (name "/COL0_A") (class "Default")
      (node (ref "R10") (pin "1") (pinfunction "1_1") (pintype "passive"))
      (node (ref "U16") (pin "15") (pinfunction "QA_15") (pintype "tri_state"))
    )
    (net (code "12") (name "/COL0_B") (class "Default")
      (node (ref "R25") (pin "1") (pinfunction "1_1") (pintype "passive"))
      (node (ref "U17") (pin "7") (pinfunction "QH_7") (pintype "tri_state"))
    )
    (net (code "13") (name "/COL0_C") (class "Default")
      (node (ref "R23") (pin "1") (pinfunction "1_1") (pintype "passive"))
      (node (ref "U17") (pin "5") (pinfunction "QF_5") (pintype "tri_state"))
    )
    (net (code "14") (name "/COL0_D") (class "Default")
      (node (ref "R20") (pin "1") (pinfunction "1_1") (pintype "passive"))
      (node (ref "U17") (pin "2") (pinfunction "QC_2") (pintype "tri_state"))
    )
    (net (code "15") (name "/COL0_E") (class "Default")
      (node (ref "R19") (pin "1") (pinfunction "1_1") (pintype "passive"))
      (node (ref "U17") (pin "1") (pinfunction "QB_1") (pintype "tri_state"))
    )
    (net (code "16") (name "/COL0_F") (class "Default")
      (node (ref "R18") (pin "1") (pinfunction "1_1") (pintype "passive"))
      (node (ref "U17") (pin "15") (pinfunction "QA_15") (pintype "tri_state"))
    )
    (net (code "17") (name "/COL0_G") (class "Default")
      (node (ref "R17") (pin "1") (pinfunction "1_1") (pintype "passive"))
      (node (ref "U16") (pin "7") (pinfunction "QH_7") (pintype "tri_state"))
    )
    (net (code "18") (name "/COL0_H") (class "Default")
      (node (ref "R13") (pin "1") (pinfunction "1_1") (pintype "passive"))
      (node (ref "U16") (pin "3") (pinfunction "QD_3") (pintype "tri_state"))
    )
    (net (code "19") (name "/COL0_K") (class "Default")
      (node (ref "R12") (pin "1") (pinfunction "1_1") (pintype "passive"))
      (node (ref "U16") (pin "2") (pinfunction "QC_2") (pintype "tri_state"))
    )
    (net (code "20") (name "/COL0_M") (class "Default")
      (node (ref "R11") (pin "1") (pinfunction "1_1") (pintype "passive"))
      (node (ref "U16") (pin "1") (pinfunction "QB_1") (pintype "tri_state"))
    )
    (net (code "21") (name "/COL0_N") (class "Default")
      (node (ref "R24") (pin "1") (pinfunction "1_1") (pintype "passive"))
      (node (ref "U17") (pin "6") (pinfunction "QG_6") (pintype "tri_state"))
    )
    (net (code "22") (name "/COL0_P") (class "Default")
      (node (ref "R22") (pin "1") (pinfunction "1_1") (pintype "passive"))
      (node (ref "U17") (pin "4") (pinfunction "QE_4") (pintype "tri_state"))
    )
    (net (code "23") (name "/COL0_R") (class "Default")
      (node (ref "R21") (pin "1") (pinfunction "1_1") (pintype "passive"))
      (node (ref "U17") (pin "3") (pinfunction "QD_3") (pintype "tri_state"))
    )
    (net (code "24") (name "/COL0_S") (class "Default")
      (node (ref "R15") (pin "1") (pinfunction "1_1") (pintype "passive"))
      (node (ref "U16") (pin "5") (pinfunction "QF_5") (pintype "tri_state"))
    )
    (net (code "25") (name "/COL0_T") (class "Default")
      (node (ref "R16") (pin "1") (pinfunction "1_1") (pintype "passive"))
      (node (ref "U16") (pin "6") (pinfunction "QG_6") (pintype "tri_state"))
    )
    (net (code "26") (name "/COL0_U") (class "Default")
      (node (ref "R14") (pin "1") (pinfunction "1_1") (pintype "passive"))
      (node (ref "U16") (pin "4") (pinfunction "QE_4") (pintype "tri_state"))
    )
    (net (code "27") (name "/COL1_A") (class "Default")
      (node (ref "R26") (pin "1") (pinfunction "1_1") (pintype "passive"))
      (node (ref "U18") (pin "15") (pinfunction "QA_15") (pintype "tri_state"))
    )
    (net (code "28") (name "/COL1_B") (class "Default")
      (node (ref "R41") (pin "1") (pinfunction "1_1") (pintype "passive"))
      (node (ref "U19") (pin "7") (pinfunction "QH_7") (pintype "tri_state"))
    )
    (net (code "29") (name "/COL1_C") (class "Default")
      (node (ref "R39") (pin "1") (pinfunction "1_1") (pintype "passive"))
      (node (ref "U19") (pin "5") (pinfunction "QF_5") (pintype "tri_state"))
    )
    (net (code "30") (name "/COL1_D") (class "Default")
      (node (ref "R36") (pin "1") (pinfunction "1_1") (pintype "passive"))
      (node (ref "U19") (pin "2") (pinfunction "QC_2") (pintype "tri_state"))
    )
    (net (code "31") (name "/COL1_E") (class "Default")
      (node (ref "R35") (pin "1") (pinfunction "1_1") (pintype "passive"))
      (node (ref "U19") (pin "1") (pinfunction "QB_1") (pintype "tri_state"))
    )
    (net (code "32") (name "/COL1_F") (class "Default")
      (node (ref "R34") (pin "1") (pinfunction "1_1") (pintype "passive"))
      (node (ref "U19") (pin "15") (pinfunction "QA_15") (pintype "tri_state"))
    )
    (net (code "33") (name "/COL1_G") (class "Default")
      (node (ref "R33") (pin "1") (pinfunction "1_1") (pintype "passive"))
      (node (ref "U18") (pin "7") (pinfunction "QH_7") (pintype "tri_state"))
    )
    (net (code "34") (name "/COL1_H") (class "Default")
      (node (ref "R29") (pin "1") (pinfunction "1_1") (pintype "passive"))
      (node (ref "U18") (pin "3") (pinfunction "QD_3") (pintype "tri_state"))
    )
    (net (code "35") (name "/COL1_K") (class "Default")
      (node (ref "R28") (pin "1") (pinfunction "1_1") (pintype "passive"))
      (node (ref "U18") (pin "2") (pinfunction "QC_2") (pintype "tri_state"))
    )
    (net (code "36") (name "/COL1_M") (class "Default")
      (node (ref "R27") (pin "1") (pinfunction "1_1") (pintype "passive"))
      (node (ref "U18") (pin "1") (pinfunction "QB_1") (pintype "tri_state"))
    )
    (net (code "37") (name "/COL1_N") (class "Default")
      (node (ref "R40") (pin "1") (pinfunction "1_1") (pintype "passive"))
      (node (ref "U19") (pin "6") (pinfunction "QG_6") (pintype "tri_state"))
    )
    (net (code "38") (name "/COL1_P") (class "Default")
      (node (ref "R38") (pin "1") (pinfunction "1_1") (pintype "passive"))
      (node (ref "U19") (pin "4") (pinfunction "QE_4") (pintype "tri_state"))
    )
    (net (code "39") (name "/COL1_R") (class "Default")
      (node (ref "R37") (pin "1") (pinfunction "1_1") (pintype "passive"))
      (node (ref "U19") (pin "3") (pinfunction "QD_3") (pintype "tri_state"))
    )
    (net (code "40") (name "/COL1_S") (class "Default")
      (node (ref "R31") (pin "1") (pinfunction "1_1") (pintype "passive"))
      (node (ref "U18") (pin "5") (pinfunction "QF_5") (pintype "tri_state"))
    )
    (net (code "41") (name "/COL1_T") (class "Default")
      (node (ref "R32") (pin "1") (pinfunction "1_1") (pintype "passive"))
      (node (ref "U18") (pin "6") (pinfunction "QG_6") (pintype "tri_state"))
    )
    (net (code "42") (name "/COL1_U") (class "Default")
      (node (ref "R30") (pin "1") (pinfunction "1_1") (pintype "passive"))
      (node (ref "U18") (pin "4") (pinfunction "QE_4") (pintype "tri_state"))
    )
    (net (code "43") (name "/COL2_A") (class "Default")
      (node (ref "R42") (pin "1") (pinfunction "1_1") (pintype "passive"))
      (node (ref "U20") (pin "15") (pinfunction "QA_15") (pintype "tri_state"))
    )
    (net (code "44") (name "/COL2_B") (class "Default")
      (node (ref "R57") (pin "1") (pinfunction "1_1") (pintype "passive"))
      (node (ref "U21") (pin "7") (pinfunction "QH_7") (pintype "tri_state"))
    )
    (net (code "45") (name "/COL2_C") (class "Default")
      (node (ref "R55") (pin "1") (pinfunction "1_1") (pintype "passive"))
      (node (ref "U21") (pin "5") (pinfunction "QF_5") (pintype "tri_state"))
    )
    (net (code "46") (name "/COL2_D") (class "Default")
      (node (ref "R52") (pin "1") (pinfunction "1_1") (pintype "passive"))
      (node (ref "U21") (pin "2") (pinfunction "QC_2") (pintype "tri_state"))
    )
    (net (code "47") (name "/COL2_E") (class "Default")
      (node (ref "R51") (pin "1") (pinfunction "1_1") (pintype "passive"))
      (node (ref "U21") (pin "1") (pinfunction "QB_1") (pintype "tri_state"))
    )
    (net (code "48") (name "/COL2_F") (class "Default")
      (node (ref "R50") (pin "1") (pinfunction "1_1") (pintype "passive"))
      (node (ref "U21") (pin "15") (pinfunction "QA_15") (pintype "tri_state"))
    )
    (net (code "49") (name "/COL2_G") (class "Default")
      (node (ref "R49") (pin "1") (pinfunction "1_1") (pintype "passive"))
      (node (ref "U20") (pin "7") (pinfunction "QH_7") (pintype "tri_state"))
    )
    (net (code "50") (name "/COL2_H") (class "Default")
      (node (ref "R45") (pin "1") (pinfunction "1_1") (pintype "passive"))
      (node (ref "U20") (pin "3") (pinfunction "QD_3") (pintype "tri_state"))
    )
    (net (code "51") (name "/COL2_K") (class "Default")
      (node (ref "R44") (pin "1") (pinfunction "1_1") (pintype "passive"))
      (node (ref "U20") (pin "2") (pinfunction "QC_2") (pintype "tri_state"))
    )
    (net (code "52") (name "/COL2_M") (class "Default")
      (node (ref "R43") (pin "1") (pinfunction "1_1") (pintype "passive"))
      (node (ref "U20") (pin "1") (pinfunction "QB_1") (pintype "tri_state"))
    )
    (net (code "53") (name "/COL2_N") (class "Default")
      (node (ref "R56") (pin "1") (pinfunction "1_1") (pintype "passive"))
      (node (ref "U21") (pin "6") (pinfunction "QG_6") (pintype "tri_state"))
    )
    (net (code "54") (name "/COL2_P") (class "Default")
      (node (ref "R54") (pin "1") (pinfunction "1_1") (pintype "passive"))
      (node (ref "U21") (pin "4") (pinfunction "QE_4") (pintype "tri_state"))
    )
    (net (code "55") (name "/COL2_R") (class "Default")
      (node (ref "R53") (pin "1") (pinfunction "1_1") (pintype "passive"))
      (node (ref "U21") (pin "3") (pinfunction "QD_3") (pintype "tri_state"))
    )
    (net (code "56") (name "/COL2_S") (class "Default")
      (node (ref "R47") (pin "1") (pinfunction "1_1") (pintype "passive"))
      (node (ref "U20") (pin "5") (pinfunction "QF_5") (pintype "tri_state"))
    )
    (net (code "57") (name "/COL2_T") (class "Default")
      (node (ref "R48") (pin "1") (pinfunction "1_1") (pintype "passive"))
      (node (ref "U20") (pin "6") (pinfunction "QG_6") (pintype "tri_state"))
    )
    (net (code "58") (name "/COL2_U") (class "Default")
      (node (ref "R46") (pin "1") (pinfunction "1_1") (pintype "passive"))
      (node (ref "U20") (pin "4") (pinfunction "QE_4") (pintype "tri_state"))
    )
    (net (code "59") (name "/COL3_A") (class "Default")
      (node (ref "R58") (pin "1") (pinfunction "1_1") (pintype "passive"))
      (node (ref "U22") (pin "15") (pinfunction "QA_15") (pintype "tri_state"))
    )
    (net (code "60") (name "/COL3_B") (class "Default")
      (node (ref "R73") (pin "1") (pinfunction "1_1") (pintype "passive"))
      (node (ref "U23") (pin "7") (pinfunction "QH_7") (pintype "tri_state"))
    )
    (net (code "61") (name "/COL3_C") (class "Default")
      (node (ref "R71") (pin "1") (pinfunction "1_1") (pintype "passive"))
      (node (ref "U23") (pin "5") (pinfunction "QF_5") (pintype "tri_state"))
    )
    (net (code "62") (name "/COL3_D") (class "Default")
      (node (ref "R68") (pin "1") (pinfunction "1_1") (pintype "passive"))
      (node (ref "U23") (pin "2") (pinfunction "QC_2") (pintype "tri_state"))
    )
    (net (code "63") (name "/COL3_E") (class "Default")
      (node (ref "R67") (pin "1") (pinfunction "1_1") (pintype "passive"))
      (node (ref "U23") (pin "1") (pinfunction "QB_1") (pintype "tri_state"))
    )
    (net (code "64") (name "/COL3_F") (class "Default")
      (node (ref "R66") (pin "1") (pinfunction "1_1") (pintype "passive"))
      (node (ref "U23") (pin "15") (pinfunction "QA_15") (pintype "tri_state"))
    )
    (net (code "65") (name "/COL3_G") (class "Default")
      (node (ref "R65") (pin "1") (pinfunction "1_1") (pintype "passive"))
      (node (ref "U22") (pin "7") (pinfunction "QH_7") (pintype "tri_state"))
    )
    (net (code "66") (name "/COL3_H") (class "Default")
      (node (ref "R61") (pin "1") (pinfunction "1_1") (pintype "passive"))
      (node (ref "U22") (pin "3") (pinfunction "QD_3") (pintype "tri_state"))
    )
    (net (code "67") (name "/COL3_K") (class "Default")
      (node (ref "R60") (pin "1") (pinfunction "1_1") (pintype "passive"))
      (node (ref "U22") (pin "2") (pinfunction "QC_2") (pintype "tri_state"))
    )
    (net (code "68") (name "/COL3_M") (class "Default")
      (node (ref "R59") (pin "1") (pinfunction "1_1") (pintype "passive"))
      (node (ref "U22") (pin "1") (pinfunction "QB_1") (pintype "tri_state"))
    )
    (net (code "69") (name "/COL3_N") (class "Default")
      (node (ref "R72") (pin "1") (pinfunction "1_1") (pintype "passive"))
      (node (ref "U23") (pin "6") (pinfunction "QG_6") (pintype "tri_state"))
    )
    (net (code "70") (name "/COL3_P") (class "Default")
      (node (ref "R70") (pin "1") (pinfunction "1_1") (pintype "passive"))
      (node (ref "U23") (pin "4") (pinfunction "QE_4") (pintype "tri_state"))
    )
    (net (code "71") (name "/COL3_R") (class "Default")
      (node (ref "R69") (pin "1") (pinfunction "1_1") (pintype "passive"))
      (node (ref "U23") (pin "3") (pinfunction "QD_3") (pintype "tri_state"))
    )
    (net (code "72") (name "/COL3_S") (class "Default")
      (node (ref "R63") (pin "1") (pinfunction "1_1") (pintype "passive"))
      (node (ref "U22") (pin "5") (pinfunction "QF_5") (pintype "tri_state"))
    )
    (net (code "73") (name "/COL3_T") (class "Default")
      (node (ref "R64") (pin "1") (pinfunction "1_1") (pintype "passive"))
      (node (ref "U22") (pin "6") (pinfunction "QG_6") (pintype "tri_state"))
    )
    (net (code "74") (name "/COL3_U") (class "Default")
      (node (ref "R62") (pin "1") (pinfunction "1_1") (pintype "passive"))
      (node (ref "U22") (pin "4") (pinfunction "QE_4") (pintype "tri_state"))
    )
    (net (code "75") (name "/COL4_A") (class "Default")
      (node (ref "R74") (pin "1") (pinfunction "1_1") (pintype "passive"))
      (node (ref "U24") (pin "15") (pinfunction "QA_15") (pintype "tri_state"))
    )
    (net (code "76") (name "/COL4_B") (class "Default")
      (node (ref "R89") (pin "1") (pinfunction "1_1") (pintype "passive"))
      (node (ref "U25") (pin "7") (pinfunction "QH_7") (pintype "tri_state"))
    )
    (net (code "77") (name "/COL4_C") (class "Default")
      (node (ref "R87") (pin "1") (pinfunction "1_1") (pintype "passive"))
      (node (ref "U25") (pin "5") (pinfunction "QF_5") (pintype "tri_state"))
    )
    (net (code "78") (name "/COL4_D") (class "Default")
      (node (ref "R84") (pin "1") (pinfunction "1_1") (pintype "passive"))
      (node (ref "U25") (pin "2") (pinfunction "QC_2") (pintype "tri_state"))
    )
    (net (code "79") (name "/COL4_E") (class "Default")
      (node (ref "R83") (pin "1") (pinfunction "1_1") (pintype "passive"))
      (node (ref "U25") (pin "1") (pinfunction "QB_1") (pintype "tri_state"))
    )
    (net (code "80") (name "/COL4_F") (class "Default")
      (node (ref "R82") (pin "1") (pinfunction "1_1") (pintype "passive"))
      (node (ref "U25") (pin "15") (pinfunction "QA_15") (pintype "tri_state"))
    )
    (net (code "81") (name "/COL4_G") (class "Default")
      (node (ref "R81") (pin "1") (pinfunction "1_1") (pintype "passive"))
      (node (ref "U24") (pin "7") (pinfunction "QH_7") (pintype "tri_state"))
    )
    (net (code "82") (name "/COL4_H") (class "Default")
      (node (ref "R77") (pin "1") (pinfunction "1_1") (pintype "passive"))
      (node (ref "U24") (pin "3") (pinfunction "QD_3") (pintype "tri_state"))
    )
    (net (code "83") (name "/COL4_K") (class "Default")
      (node (ref "R76") (pin "1") (pinfunction "1_1") (pintype "passive"))
      (node (ref "U24") (pin "2") (pinfunction "QC_2") (pintype "tri_state"))
    )
    (net (code "84") (name "/COL4_M") (class "Default")
      (node (ref "R75") (pin "1") (pinfunction "1_1") (pintype "passive"))
      (node (ref "U24") (pin "1") (pinfunction "QB_1") (pintype "tri_state"))
    )
    (net (code "85") (name "/COL4_N") (class "Default")
      (node (ref "R88") (pin "1") (pinfunction "1_1") (pintype "passive"))
      (node (ref "U25") (pin "6") (pinfunction "QG_6") (pintype "tri_state"))
    )
    (net (code "86") (name "/COL4_P") (class "Default")
      (node (ref "R86") (pin "1") (pinfunction "1_1") (pintype "passive"))
      (node (ref "U25") (pin "4") (pinfunction "QE_4") (pintype "tri_state"))
    )
    (net (code "87") (name "/COL4_R") (class "Default")
      (node (ref "R85") (pin "1") (pinfunction "1_1") (pintype "passive"))
      (node (ref "U25") (pin "3") (pinfunction "QD_3") (pintype "tri_state"))
    )
    (net (code "88") (name "/COL4_S") (class "Default")
      (node (ref "R79") (pin "1") (pinfunction "1_1") (pintype "passive"))
      (node (ref "U24") (pin "5") (pinfunction "QF_5") (pintype "tri_state"))
    )
    (net (code "89") (name "/COL4_T") (class "Default")
      (node (ref "R80") (pin "1") (pinfunction "1_1") (pintype "passive"))
      (node (ref "U24") (pin "6") (pinfunction "QG_6") (pintype "tri_state"))
    )
    (net (code "90") (name "/COL4_U") (class "Default")
      (node (ref "R78") (pin "1") (pinfunction "1_1") (pintype "passive"))
      (node (ref "U24") (pin "4") (pinfunction "QE_4") (pintype "tri_state"))
    )
    (net (code "91") (name "/COL5\\_B") (class "Default")
      (node (ref "R105") (pin "1") (pinfunction "1_1") (pintype "passive"))
      (node (ref "U27") (pin "7") (pinfunction "QH_7") (pintype "tri_state"))
    )
    (net (code "92") (name "/COL5_A") (class "Default")
      (node (ref "R90") (pin "1") (pinfunction "1_1") (pintype "passive"))
      (node (ref "U26") (pin "15") (pinfunction "QA_15") (pintype "tri_state"))
    )
    (net (code "93") (name "/COL5_C") (class "Default")
      (node (ref "R103") (pin "1") (pinfunction "1_1") (pintype "passive"))
      (node (ref "U27") (pin "5") (pinfunction "QF_5") (pintype "tri_state"))
    )
    (net (code "94") (name "/COL5_D") (class "Default")
      (node (ref "R100") (pin "1") (pinfunction "1_1") (pintype "passive"))
      (node (ref "U27") (pin "2") (pinfunction "QC_2") (pintype "tri_state"))
    )
    (net (code "95") (name "/COL5_E") (class "Default")
      (node (ref "R99") (pin "1") (pinfunction "1_1") (pintype "passive"))
      (node (ref "U27") (pin "1") (pinfunction "QB_1") (pintype "tri_state"))
    )
    (net (code "96") (name "/COL5_F") (class "Default")
      (node (ref "R98") (pin "1") (pinfunction "1_1") (pintype "passive"))
      (node (ref "U27") (pin "15") (pinfunction "QA_15") (pintype "tri_state"))
    )
    (net (code "97") (name "/COL5_G") (class "Default")
      (node (ref "R97") (pin "1") (pinfunction "1_1") (pintype "passive"))
      (node (ref "U26") (pin "7") (pinfunction "QH_7") (pintype "tri_state"))
    )
    (net (code "98") (name "/COL5_H") (class "Default")
      (node (ref "R93") (pin "1") (pinfunction "1_1") (pintype "passive"))
      (node (ref "U26") (pin "3") (pinfunction "QD_3") (pintype "tri_state"))
    )
    (net (code "99") (name "/COL5_K") (class "Default")
      (node (ref "R92") (pin "1") (pinfunction "1_1") (pintype "passive"))
      (node (ref "U26") (pin "2") (pinfunction "QC_2") (pintype "tri_state"))
    )
    (net (code "100") (name "/COL5_M") (class "Default")
      (node (ref "R91") (pin "1") (pinfunction "1_1") (pintype "passive"))
      (node (ref "U26") (pin "1") (pinfunction "QB_1") (pintype "tri_state"))
    )
    (net (code "101") (name "/COL5_N") (class "Default")
      (node (ref "R104") (pin "1") (pinfunction "1_1") (pintype "passive"))
      (node (ref "U27") (pin "6") (pinfunction "QG_6") (pintype "tri_state"))
    )
    (net (code "102") (name "/COL5_P") (class "Default")
      (node (ref "R102") (pin "1") (pinfunction "1_1") (pintype "passive"))
      (node (ref "U27") (pin "4") (pinfunction "QE_4") (pintype "tri_state"))
    )
    (net (code "103") (name "/COL5_R") (class "Default")
      (node (ref "R101") (pin "1") (pinfunction "1_1") (pintype "passive"))
      (node (ref "U27") (pin "3") (pinfunction "QD_3") (pintype "tri_state"))
    )
    (net (code "104") (name "/COL5_S") (class "Default")
      (node (ref "R95") (pin "1") (pinfunction "1_1") (pintype "passive"))
      (node (ref "U26") (pin "5") (pinfunction "QF_5") (pintype "tri_state"))
    )
    (net (code "105") (name "/COL5_T") (class "Default")
      (node (ref "R96") (pin "1") (pinfunction "1_1") (pintype "passive"))
      (node (ref "U26") (pin "6") (pinfunction "QG_6") (pintype "tri_state"))
    )
    (net (code "106") (name "/COL5_U") (class "Default")
      (node (ref "R94") (pin "1") (pinfunction "1_1") (pintype "passive"))
      (node (ref "U26") (pin "4") (pinfunction "QE_4") (pintype "tri_state"))
    )
    (net (code "107") (name "/COL6_A") (class "Default")
      (node (ref "R106") (pin "1") (pinfunction "1_1") (pintype "passive"))
      (node (ref "U28") (pin "15") (pinfunction "QA_15") (pintype "tri_state"))
    )
    (net (code "108") (name "/COL6_B") (class "Default")
      (node (ref "R121") (pin "1") (pinfunction "1_1") (pintype "passive"))
      (node (ref "U29") (pin "7") (pinfunction "QH_7") (pintype "tri_state"))
    )
    (net (code "109") (name "/COL6_C") (class "Default")
      (node (ref "R119") (pin "1") (pinfunction "1_1") (pintype "passive"))
      (node (ref "U29") (pin "5") (pinfunction "QF_5") (pintype "tri_state"))
    )
    (net (code "110") (name "/COL6_D") (class "Default")
      (node (ref "R116") (pin "1") (pinfunction "1_1") (pintype "passive"))
      (node (ref "U29") (pin "2") (pinfunction "QC_2") (pintype "tri_state"))
    )
    (net (code "111") (name "/COL6_E") (class "Default")
      (node (ref "R115") (pin "1") (pinfunction "1_1") (pintype "passive"))
      (node (ref "U29") (pin "1") (pinfunction "QB_1") (pintype "tri_state"))
    )
    (net (code "112") (name "/COL6_F") (class "Default")
      (node (ref "R114") (pin "1") (pinfunction "1_1") (pintype "passive"))
      (node (ref "U29") (pin "15") (pinfunction "QA_15") (pintype "tri_state"))
    )
    (net (code "113") (name "/COL6_G") (class "Default")
      (node (ref "R113") (pin "1") (pinfunction "1_1") (pintype "passive"))
      (node (ref "U28") (pin "7") (pinfunction "QH_7") (pintype "tri_state"))
    )
    (net (code "114") (name "/COL6_H") (class "Default")
      (node (ref "R109") (pin "1") (pinfunction "1_1") (pintype "passive"))
      (node (ref "U28") (pin "3") (pinfunction "QD_3") (pintype "tri_state"))
    )
    (net (code "115") (name "/COL6_K") (class "Default")
      (node (ref "R108") (pin "1") (pinfunction "1_1") (pintype "passive"))
      (node (ref "U28") (pin "2") (pinfunction "QC_2") (pintype "tri_state"))
    )
    (net (code "116") (name "/COL6_M") (class "Default")
      (node (ref "R107") (pin "1") (pinfunction "1_1") (pintype "passive"))
      (node (ref "U28") (pin "1") (pinfunction "QB_1") (pintype "tri_state"))
    )
    (net (code "117") (name "/COL6_N") (class "Default")
      (node (ref "R120") (pin "1") (pinfunction "1_1") (pintype "passive"))
      (node (ref "U29") (pin "6") (pinfunction "QG_6") (pintype "tri_state"))
    )
    (net (code "118") (name "/COL6_P") (class "Default")
      (node (ref "R118") (pin "1") (pinfunction "1_1") (pintype "passive"))
      (node (ref "U29") (pin "4") (pinfunction "QE_4") (pintype "tri_state"))
    )
    (net (code "119") (name "/COL6_R") (class "Default")
      (node (ref "R117") (pin "1") (pinfunction "1_1") (pintype "passive"))
      (node (ref "U29") (pin "3") (pinfunction "QD_3") (pintype "tri_state"))
    )
    (net (code "120") (name "/COL6_S") (class "Default")
      (node (ref "R111") (pin "1") (pinfunction "1_1") (pintype "passive"))
      (node (ref "U28") (pin "5") (pinfunction "QF_5") (pintype "tri_state"))
    )
    (net (code "121") (name "/COL6_T") (class "Default")
      (node (ref "R112") (pin "1") (pinfunction "1_1") (pintype "passive"))
      (node (ref "U28") (pin "6") (pinfunction "QG_6") (pintype "tri_state"))
    )
    (net (code "122") (name "/COL6_U") (class "Default")
      (node (ref "R110") (pin "1") (pinfunction "1_1") (pintype "passive"))
      (node (ref "U28") (pin "4") (pinfunction "QE_4") (pintype "tri_state"))
    )
    (net (code "123") (name "/COL7\\_F") (class "Default")
      (node (ref "R130") (pin "1") (pinfunction "1_1") (pintype "passive"))
      (node (ref "U31") (pin "15") (pinfunction "QA_15") (pintype "tri_state"))
    )
    (net (code "124") (name "/COL7_A") (class "Default")
      (node (ref "R122") (pin "1") (pinfunction "1_1") (pintype "passive"))
      (node (ref "U30") (pin "15") (pinfunction "QA_15") (pintype "tri_state"))
    )
    (net (code "125") (name "/COL7_B") (class "Default")
      (node (ref "R137") (pin "1") (pinfunction "1_1") (pintype "passive"))
      (node (ref "U31") (pin "7") (pinfunction "QH_7") (pintype "tri_state"))
    )
    (net (code "126") (name "/COL7_C") (class "Default")
      (node (ref "R135") (pin "1") (pinfunction "1_1") (pintype "passive"))
      (node (ref "U31") (pin "5") (pinfunction "QF_5") (pintype "tri_state"))
    )
    (net (code "127") (name "/COL7_D") (class "Default")
      (node (ref "R132") (pin "1") (pinfunction "1_1") (pintype "passive"))
      (node (ref "U31") (pin "2") (pinfunction "QC_2") (pintype "tri_state"))
    )
    (net (code "128") (name "/COL7_E") (class "Default")
      (node (ref "R131") (pin "1") (pinfunction "1_1") (pintype "passive"))
      (node (ref "U31") (pin "1") (pinfunction "QB_1") (pintype "tri_state"))
    )
    (net (code "129") (name "/COL7_G") (class "Default")
      (node (ref "R129") (pin "1") (pinfunction "1_1") (pintype "passive"))
      (node (ref "U30") (pin "7") (pinfunction "QH_7") (pintype "tri_state"))
    )
    (net (code "130") (name "/COL7_H") (class "Default")
      (node (ref "R125") (pin "1") (pinfunction "1_1") (pintype "passive"))
      (node (ref "U30") (pin "3") (pinfunction "QD_3") (pintype "tri_state"))
    )
    (net (code "131") (name "/COL7_K") (class "Default")
      (node (ref "R124") (pin "1") (pinfunction "1_1") (pintype "passive"))
      (node (ref "U30") (pin "2") (pinfunction "QC_2") (pintype "tri_state"))
    )
    (net (code "132") (name "/COL7_M") (class "Default")
      (node (ref "R123") (pin "1") (pinfunction "1_1") (pintype "passive"))
      (node (ref "U30") (pin "1") (pinfunction "QB_1") (pintype "tri_state"))
    )
    (net (code "133") (name "/COL7_N") (class "Default")
      (node (ref "R136") (pin "1") (pinfunction "1_1") (pintype "passive"))
      (node (ref "U31") (pin "6") (pinfunction "QG_6") (pintype "tri_state"))
    )
    (net (code "134") (name "/COL7_P") (class "Default")
      (node (ref "R134") (pin "1") (pinfunction "1_1") (pintype "passive"))
      (node (ref "U31") (pin "4") (pinfunction "QE_4") (pintype "tri_state"))
    )
    (net (code "135") (name "/COL7_R") (class "Default")
      (node (ref "R133") (pin "1") (pinfunction "1_1") (pintype "passive"))
      (node (ref "U31") (pin "3") (pinfunction "QD_3") (pintype "tri_state"))
    )
    (net (code "136") (name "/COL7_S") (class "Default")
      (node (ref "R127") (pin "1") (pinfunction "1_1") (pintype "passive"))
      (node (ref "U30") (pin "5") (pinfunction "QF_5") (pintype "tri_state"))
    )
    (net (code "137") (name "/COL7_T") (class "Default")
      (node (ref "R128") (pin "1") (pinfunction "1_1") (pintype "passive"))
      (node (ref "U30") (pin "6") (pinfunction "QG_6") (pintype "tri_state"))
    )
    (net (code "138") (name "/COL7_U") (class "Default")
      (node (ref "R126") (pin "1") (pinfunction "1_1") (pintype "passive"))
      (node (ref "U30") (pin "4") (pinfunction "QE_4") (pintype "tri_state"))
    )
    (net (code "139") (name "/D0") (class "Default")
      (node (ref "U1") (pin "18") (pinfunction "B1_18") (pintype "bidirectional"))
      (node (ref "U11") (pin "2") (pinfunction "A_2") (pintype "input"))
      (node (ref "U13") (pin "2") (pinfunction "1D_2") (pintype "input"))
    )
    (net (code "140") (name "/D1") (class "Default")
      (node (ref "U1") (pin "17") (pinfunction "B2_17") (pintype "bidirectional"))
      (node (ref "U11") (pin "3") (pinfunction "B_3") (pintype "input"))
      (node (ref "U13") (pin "3") (pinfunction "2D_3") (pintype "input"))
    )
    (net (code "141") (name "/D2") (class "Default")
      (node (ref "U1") (pin "16") (pinfunction "B3_16") (pintype "bidirectional"))
      (node (ref "U11") (pin "4") (pinfunction "C_4") (pintype "input"))
      (node (ref "U13") (pin "4") (pinfunction "3D_4") (pintype "input"))
    )
    (net (code "142") (name "/D3") (class "Default")
      (node (ref "U1") (pin "15") (pinfunction "B4_15") (pintype "bidirectional"))
      (node (ref "U11") (pin "5") (pinfunction "D_5") (pintype "input"))
      (node (ref "U13") (pin "5") (pinfunction "4D_5") (pintype "input"))
    )
    (net (code "143") (name "/D4") (class "Default")
      (node (ref "U1") (pin "14") (pinfunction "B5_14") (pintype "bidirectional"))
      (node (ref "U11") (pin "10") (pinfunction "E_10") (pintype "input"))
      (node (ref "U13") (pin "6") (pinfunction "5D_6") (pintype "input"))
    )
    (net (code "144") (name "/D5") (class "Default")
      (node (ref "U1") (pin "13") (pinfunction "B6_13") (pintype "bidirectional"))
      (node (ref "U11") (pin "11") (pinfunction "F_11") (pintype "input"))
      (node (ref "U13") (pin "7") (pinfunction "6D_7") (pintype "input"))
    )
    (net (code "145") (name "/D6") (class "Default")
      (node (ref "U1") (pin "12") (pinfunction "B7_12") (pintype "bidirectional"))
      (node (ref "U11") (pin "12") (pinfunction "G_12") (pintype "input"))
      (node (ref "U13") (pin "8") (pinfunction "7D_8") (pintype "input"))
    )
    (net (code "146") (name "/D7") (class "Default")
      (node (ref "U1") (pin "11") (pinfunction "B8_11") (pintype "bidirectional"))
      (node (ref "U11") (pin "14") (pinfunction "H_14") (pintype "input"))
      (node (ref "U13") (pin "9") (pinfunction "8D_9") (pintype "input"))
    )
    (net (code "147") (name "/DP0") (class "Default")
      (node (ref "R2") (pin "1") (pinfunction "1_1") (pintype "passive"))
      (node (ref "U15") (pin "15") (pinfunction "QA_15") (pintype "tri_state"))
    )
    (net (code "148") (name "/DP1") (class "Default")
      (node (ref "R3") (pin "1") (pinfunction "1_1") (pintype "passive"))
      (node (ref "U15") (pin "1") (pinfunction "QB_1") (pintype "tri_state"))
    )
    (net (code "149") (name "/DP2") (class "Default")
      (node (ref "R4") (pin "1") (pinfunction "1_1") (pintype "passive"))
      (node (ref "U15") (pin "2") (pinfunction "QC_2") (pintype "tri_state"))
    )
    (net (code "150") (name "/DP3") (class "Default")
      (node (ref "R5") (pin "1") (pinfunction "1_1") (pintype "passive"))
      (node (ref "U15") (pin "3") (pinfunction "QD_3") (pintype "tri_state"))
    )
    (net (code "151") (name "/DP4") (class "Default")
      (node (ref "R6") (pin "1") (pinfunction "1_1") (pintype "passive"))
      (node (ref "U15") (pin "4") (pinfunction "QE_4") (pintype "tri_state"))
    )
    (net (code "152") (name "/DP5") (class "Default")
      (node (ref "R7") (pin "1") (pinfunction "1_1") (pintype "passive"))
      (node (ref "U15") (pin "5") (pinfunction "QF_5") (pintype "tri_state"))
    )
    (net (code "153") (name "/DP6") (class "Default")
      (node (ref "R8") (pin "1") (pinfunction "1_1") (pintype "passive"))
      (node (ref "U15") (pin "6") (pinfunction "QG_6") (pintype "tri_state"))
    )
    (net (code "154") (name "/DP7") (class "Default")
      (node (ref "R9") (pin "1") (pinfunction "1_1") (pintype "passive"))
      (node (ref "U15") (pin "7") (pinfunction "QH_7") (pintype "tri_state"))
    )
    (net (code "155") (name "/ROW0") (class "Default")
      (node (ref "SV4") (pin "34") (pinfunction "S_34") (pintype "passive"))
      (node (ref "U14") (pin "14") (pinfunction "Y1_14") (pintype "output"))
    )
    (net (code "156") (name "/ROW1") (class "Default")
      (node (ref "SV4") (pin "35") (pinfunction "S_35") (pintype "passive"))
      (node (ref "U14") (pin "13") (pinfunction "Y2_13") (pintype "output"))
    )
    (net (code "157") (name "/ROW2") (class "Default")
      (node (ref "SV4") (pin "36") (pinfunction "S_36") (pintype "passive"))
      (node (ref "U14") (pin "12") (pinfunction "Y3_12") (pintype "output"))
    )
    (net (code "158") (name "/~{G}") (class "Default")
      (node (ref "R1") (pin "2") (pinfunction "2_2") (pintype "passive"))
      (node (ref "U15") (pin "13") (pinfunction "G_13") (pintype "input"))
      (node (ref "U16") (pin "13") (pinfunction "G_13") (pintype "input"))
      (node (ref "U17") (pin "13") (pinfunction "G_13") (pintype "input"))
      (node (ref "U18") (pin "13") (pinfunction "G_13") (pintype "input"))
      (node (ref "U19") (pin "13") (pinfunction "G_13") (pintype "input"))
      (node (ref "U20") (pin "13") (pinfunction "G_13") (pintype "input"))
      (node (ref "U21") (pin "13") (pinfunction "G_13") (pintype "input"))
      (node (ref "U22") (pin "13") (pinfunction "G_13") (pintype "input"))
      (node (ref "U23") (pin "13") (pinfunction "G_13") (pintype "input"))
      (node (ref "U24") (pin "13") (pinfunction "G_13") (pintype "input"))
      (node (ref "U25") (pin "13") (pinfunction "G_13") (pintype "input"))
      (node (ref "U26") (pin "13") (pinfunction "G_13") (pintype "input"))
      (node (ref "U27") (pin "13") (pinfunction "G_13") (pintype "input"))
      (node (ref "U28") (pin "13") (pinfunction "G_13") (pintype "input"))
      (node (ref "U29") (pin "13") (pinfunction "G_13") (pintype "input"))
      (node (ref "U30") (pin "13") (pinfunction "G_13") (pintype "input"))
      (node (ref "U31") (pin "13") (pinfunction "G_13") (pintype "input"))
    )
    (net (code "159") (name "/~{INT}") (class "Default")
      (node (ref "BUS") (pin "11") (pinfunction "S_11") (pintype "passive"))
    )
    (net (code "160") (name "/~{IORQ}") (class "Default")
      (node (ref "U10") (pin "1") (pinfunction "I0_1") (pintype "input"))
      (node (ref "U3") (pin "16") (pinfunction "B3_16") (pintype "bidirectional"))
    )
    (net (code "161") (name "/~{NMI}") (class "Default")
      (node (ref "BUS") (pin "12") (pinfunction "S_12") (pintype "passive"))
    )
    (net (code "162") (name "/~{RESET}") (class "Default")
      (node (ref "U12") (pin "1") (pinfunction "I0_1") (pintype "input"))
      (node (ref "U12") (pin "4") (pinfunction "I0_4") (pintype "input"))
      (node (ref "U15") (pin "10") (pinfunction "SCL_10") (pintype "input"))
      (node (ref "U16") (pin "10") (pinfunction "SCL_10") (pintype "input"))
      (node (ref "U17") (pin "10") (pinfunction "SCL_10") (pintype "input"))
      (node (ref "U18") (pin "10") (pinfunction "SCL_10") (pintype "input"))
      (node (ref "U19") (pin "10") (pinfunction "SCL_10") (pintype "input"))
      (node (ref "U20") (pin "10") (pinfunction "SCL_10") (pintype "input"))
      (node (ref "U21") (pin "10") (pinfunction "SCL_10") (pintype "input"))
      (node (ref "U22") (pin "10") (pinfunction "SCL_10") (pintype "input"))
      (node (ref "U23") (pin "10") (pinfunction "SCL_10") (pintype "input"))
      (node (ref "U24") (pin "10") (pinfunction "SCL_10") (pintype "input"))
      (node (ref "U25") (pin "10") (pinfunction "SCL_10") (pintype "input"))
      (node (ref "U26") (pin "10") (pinfunction "SCL_10") (pintype "input"))
      (node (ref "U27") (pin "10") (pinfunction "SCL_10") (pintype "input"))
      (node (ref "U28") (pin "10") (pinfunction "SCL_10") (pintype "input"))
      (node (ref "U29") (pin "10") (pinfunction "SCL_10") (pintype "input"))
      (node (ref "U3") (pin "12") (pinfunction "B7_12") (pintype "bidirectional"))
      (node (ref "U30") (pin "10") (pinfunction "SCL_10") (pintype "input"))
      (node (ref "U31") (pin "10") (pinfunction "SCL_10") (pintype "input"))
      (node (ref "U8") (pin "1") (pinfunction "I0_1") (pintype "input"))
    )
    (net (code "163") (name "/~{WAIT}") (class "Default")
      (node (ref "BUS") (pin "10") (pinfunction "S_10") (pintype "passive"))
    )
    (net (code "164") (name "/~{WR}") (class "Default")
      (node (ref "U10") (pin "2") (pinfunction "I1_2") (pintype "input"))
      (node (ref "U3") (pin "14") (pinfunction "B5_14") (pintype "bidirectional"))
    )
    (net (code "165") (name "GND") (class "Default")
      (node (ref "BUS") (pin "1") (pinfunction "S_1") (pintype "passive"))
      (node (ref "BUS") (pin "3") (pinfunction "S_3") (pintype "passive"))
      (node (ref "BUS") (pin "31") (pinfunction "S_31") (pintype "passive"))
      (node (ref "BUS") (pin "32") (pinfunction "S_32") (pintype "passive"))
      (node (ref "C1") (pin "-") (pinfunction "-_-") (pintype "passive"))
      (node (ref "C10") (pin "2") (pinfunction "2_2") (pintype "passive"))
      (node (ref "C11") (pin "2") (pinfunction "2_2") (pintype "passive"))
      (node (ref "C12") (pin "2") (pinfunction "2_2") (pintype "passive"))
      (node (ref "C13") (pin "2") (pinfunction "2_2") (pintype "passive"))
      (node (ref "C14") (pin "2") (pinfunction "2_2") (pintype "passive"))
      (node (ref "C15") (pin "2") (pinfunction "2_2") (pintype "passive"))
      (node (ref "C16") (pin "2") (pinfunction "2_2") (pintype "passive"))
      (node (ref "C17") (pin "2") (pinfunction "2_2") (pintype "passive"))
      (node (ref "C18") (pin "2") (pinfunction "2_2") (pintype "passive"))
      (node (ref "C19") (pin "2") (pinfunction "2_2") (pintype "passive"))
      (node (ref "C20") (pin "2") (pinfunction "2_2") (pintype "passive"))
      (node (ref "C21") (pin "2") (pinfunction "2_2") (pintype "passive"))
      (node (ref "C22") (pin "2") (pinfunction "2_2") (pintype "passive"))
      (node (ref "C23") (pin "2") (pinfunction "2_2") (pintype "passive"))
      (node (ref "C24") (pin "2") (pinfunction "2_2") (pintype "passive"))
      (node (ref "C25") (pin "2") (pinfunction "2_2") (pintype "passive"))
      (node (ref "C26") (pin "2") (pinfunction "2_2") (pintype "passive"))
      (node (ref "C27") (pin "2") (pinfunction "2_2") (pintype "passive"))
      (node (ref "C28") (pin "2") (pinfunction "2_2") (pintype "passive"))
      (node (ref "C29") (pin "2") (pinfunction "2_2") (pintype "passive"))
      (node (ref "C3") (pin "2") (pinfunction "2_2") (pintype "passive"))
      (node (ref "C30") (pin "2") (pinfunction "2_2") (pintype "passive"))
      (node (ref "C31") (pin "2") (pinfunction "2_2") (pintype "passive"))
      (node (ref "C32") (pin "2") (pinfunction "2_2") (pintype "passive"))
      (node (ref "C33") (pin "2") (pinfunction "2_2") (pintype "passive"))
      (node (ref "C4") (pin "2") (pinfunction "2_2") (pintype "passive"))
      (node (ref "C5") (pin "2") (pinfunction "2_2") (pintype "passive"))
      (node (ref "C6") (pin "2") (pinfunction "2_2") (pintype "passive"))
      (node (ref "C7") (pin "2") (pinfunction "2_2") (pintype "passive"))
      (node (ref "C8") (pin "2") (pinfunction "2_2") (pintype "passive"))
      (node (ref "C9") (pin "2") (pinfunction "2_2") (pintype "passive"))
      (node (ref "R1") (pin "1") (pinfunction "1_1") (pintype "passive"))
      (node (ref "SV4") (pin "39") (pinfunction "S_39") (pintype "passive"))
      (node (ref "SV4") (pin "40") (pinfunction "S_40") (pintype "passive"))
      (node (ref "U1") (pin "10") (pinfunction "GND_10") (pintype "power_in"))
      (node (ref "U1") (pin "19") (pinfunction "G_19") (pintype "input"))
      (node (ref "U10") (pin "10") (pinfunction "I1_10") (pintype "input"))
      (node (ref "U10") (pin "12") (pinfunction "I0_12") (pintype "input"))
      (node (ref "U10") (pin "13") (pinfunction "I1_13") (pintype "input"))
      (node (ref "U10") (pin "7") (pinfunction "GND_7") (pintype "power_in"))
      (node (ref "U10") (pin "9") (pinfunction "I0_9") (pintype "input"))
      (node (ref "U11") (pin "1") (pinfunction "SER_1") (pintype "input"))
      (node (ref "U11") (pin "6") (pinfunction "INH_6") (pintype "input"))
      (node (ref "U11") (pin "8") (pinfunction "GND_8") (pintype "power_in"))
      (node (ref "U12") (pin "10") (pinfunction "I1_10") (pintype "input"))
      (node (ref "U12") (pin "12") (pinfunction "I0_12") (pintype "input"))
      (node (ref "U12") (pin "13") (pinfunction "I1_13") (pintype "input"))
      (node (ref "U12") (pin "7") (pinfunction "GND_7") (pintype "power_in"))
      (node (ref "U12") (pin "9") (pinfunction "I0_9") (pintype "input"))
      (node (ref "U13") (pin "1") (pinfunction "OC_1") (pintype "input"))
      (node (ref "U13") (pin "10") (pinfunction "GND_10") (pintype "power_in"))
      (node (ref "U14") (pin "3") (pinfunction "C_3") (pintype "input"))
      (node (ref "U14") (pin "4") (pinfunction "G2A_4") (pintype "input"))
      (node (ref "U14") (pin "5") (pinfunction "G2B_5") (pintype "input"))
      (node (ref "U14") (pin "8") (pinfunction "GND_8") (pintype "power_in"))
      (node (ref "U15") (pin "8") (pinfunction "GND_8") (pintype "power_in"))
      (node (ref "U16") (pin "8") (pinfunction "GND_8") (pintype "power_in"))
      (node (ref "U17") (pin "8") (pinfunction "GND_8") (pintype "power_in"))
      (node (ref "U18") (pin "8") (pinfunction "GND_8") (pintype "power_in"))
      (node (ref "U19") (pin "8") (pinfunction "GND_8") (pintype "power_in"))
      (node (ref "U2") (pin "10") (pinfunction "GND_10") (pintype "power_in"))
      (node (ref "U2") (pin "19") (pinfunction "G_19") (pintype "input"))
      (node (ref "U20") (pin "8") (pinfunction "GND_8") (pintype "power_in"))
      (node (ref "U21") (pin "8") (pinfunction "GND_8") (pintype "power_in"))
      (node (ref "U22") (pin "8") (pinfunction "GND_8") (pintype "power_in"))
      (node (ref "U23") (pin "8") (pinfunction "GND_8") (pintype "power_in"))
      (node (ref "U24") (pin "8") (pinfunction "GND_8") (pintype "power_in"))
      (node (ref "U25") (pin "8") (pinfunction "GND_8") (pintype "power_in"))
      (node (ref "U26") (pin "8") (pinfunction "GND_8") (pintype "power_in"))
      (node (ref "U27") (pin "8") (pinfunction "GND_8") (pintype "power_in"))
      (node (ref "U28") (pin "8") (pinfunction "GND_8") (pintype "power_in"))
      (node (ref "U29") (pin "8") (pinfunction "GND_8") (pintype "power_in"))
      (node (ref "U3") (pin "10") (pinfunction "GND_10") (pintype "power_in"))
      (node (ref "U3") (pin "19") (pinfunction "G_19") (pintype "input"))
      (node (ref "U3") (pin "7") (pinfunction "A6_7") (pintype "bidirectional"))
      (node (ref "U30") (pin "8") (pinfunction "GND_8") (pintype "power_in"))
      (node (ref "U31") (pin "8") (pinfunction "GND_8") (pintype "power_in"))
      (node (ref "U4") (pin "10") (pinfunction "GND_10") (pintype "power_in"))
      (node (ref "U4") (pin "12") (pinfunction "Q4_12") (pintype "input"))
      (node (ref "U4") (pin "16") (pinfunction "Q6_16") (pintype "input"))
      (node (ref "U4") (pin "18") (pinfunction "Q7_18") (pintype "input"))
      (node (ref "U4") (pin "3") (pinfunction "Q0_3") (pintype "input"))
      (node (ref "U4") (pin "5") (pinfunction "Q1_5") (pintype "input"))
      (node (ref "U4") (pin "7") (pinfunction "Q2_7") (pintype "input"))
      (node (ref "U4") (pin "9") (pinfunction "Q3_9") (pintype "input"))
      (node (ref "U5") (pin "10") (pinfunction "GND_10") (pintype "power_in"))
      (node (ref "U5") (pin "12") (pinfunction "Q4_12") (pintype "input"))
      (node (ref "U5") (pin "16") (pinfunction "Q6_16") (pintype "input"))
      (node (ref "U5") (pin "18") (pinfunction "Q7_18") (pintype "input"))
      (node (ref "U5") (pin "5") (pinfunction "Q1_5") (pintype "input"))
      (node (ref "U5") (pin "7") (pinfunction "Q2_7") (pintype "input"))
      (node (ref "U5") (pin "9") (pinfunction "Q3_9") (pintype "input"))
      (node (ref "U6") (pin "11") (pinfunction "I_11") (pintype "input"))
      (node (ref "U6") (pin "13") (pinfunction "I_13") (pintype "input"))
      (node (ref "U6") (pin "7") (pinfunction "GND_7") (pintype "power_in"))
      (node (ref "U7") (pin "10") (pinfunction "PRE_10") (pintype "input"))
      (node (ref "U7") (pin "11") (pinfunction "CLK_11") (pintype "input"))
      (node (ref "U7") (pin "12") (pinfunction "D_12") (pintype "input"))
      (node (ref "U7") (pin "13") (pinfunction "CLR_13") (pintype "input"))
      (node (ref "U7") (pin "7") (pinfunction "GND_7") (pintype "power_in"))
      (node (ref "U8") (pin "7") (pinfunction "GND_7") (pintype "power_in"))
      (node (ref "U9") (pin "7") (pinfunction "GND_7") (pintype "power_in"))
    )
    (net (code "166") (name "Net-(BUSAA-S)") (class "Default")
      (node (ref "BUS") (pin "33") (pinfunction "S_33") (pintype "passive"))
      (node (ref "U2") (pin "9") (pinfunction "A8_9") (pintype "bidirectional"))
    )
    (net (code "167") (name "Net-(BUSAB-S)") (class "Default")
      (node (ref "BUS") (pin "34") (pinfunction "S_34") (pintype "passive"))
      (node (ref "U2") (pin "8") (pinfunction "A7_8") (pintype "bidirectional"))
    )
    (net (code "168") (name "Net-(BUSAC-S)") (class "Default")
      (node (ref "BUS") (pin "35") (pinfunction "S_35") (pintype "passive"))
      (node (ref "U2") (pin "7") (pinfunction "A6_7") (pintype "bidirectional"))
    )
    (net (code "169") (name "Net-(BUSAD-S)") (class "Default")
      (node (ref "BUS") (pin "36") (pinfunction "S_36") (pintype "passive"))
      (node (ref "U2") (pin "6") (pinfunction "A5_6") (pintype "bidirectional"))
    )
    (net (code "170") (name "Net-(BUSAE-S)") (class "Default")
      (node (ref "BUS") (pin "37") (pinfunction "S_37") (pintype "passive"))
      (node (ref "U2") (pin "5") (pinfunction "A4_5") (pintype "bidirectional"))
    )
    (net (code "171") (name "Net-(BUSAF-S)") (class "Default")
      (node (ref "BUS") (pin "38") (pinfunction "S_38") (pintype "passive"))
      (node (ref "U2") (pin "4") (pinfunction "A3_4") (pintype "bidirectional"))
    )
    (net (code "172") (name "Net-(BUSAG-S)") (class "Default")
      (node (ref "BUS") (pin "39") (pinfunction "S_39") (pintype "passive"))
      (node (ref "U2") (pin "3") (pinfunction "A2_3") (pintype "bidirectional"))
    )
    (net (code "173") (name "Net-(BUSAI-S)") (class "Default")
      (node (ref "BUS") (pin "40") (pinfunction "S_40") (pintype "passive"))
      (node (ref "U2") (pin "2") (pinfunction "A1_2") (pintype "bidirectional"))
    )
    (net (code "174") (name "Net-(BUSAJ-S)") (class "Default")
      (node (ref "BUS") (pin "5") (pinfunction "S_5") (pintype "passive"))
      (node (ref "U3") (pin "9") (pinfunction "A8_9") (pintype "bidirectional"))
    )
    (net (code "175") (name "Net-(BUSAK-S)") (class "Default")
      (node (ref "BUS") (pin "6") (pinfunction "S_6") (pintype "passive"))
      (node (ref "U3") (pin "8") (pinfunction "A7_8") (pintype "bidirectional"))
    )
    (net (code "176") (name "Net-(BUSAL-S)") (class "Default")
      (node (ref "BUS") (pin "7") (pinfunction "S_7") (pintype "passive"))
      (node (ref "U3") (pin "6") (pinfunction "A5_6") (pintype "bidirectional"))
    )
    (net (code "177") (name "Net-(BUSAM-S)") (class "Default")
      (node (ref "BUS") (pin "8") (pinfunction "S_8") (pintype "passive"))
      (node (ref "U3") (pin "5") (pinfunction "A4_5") (pintype "bidirectional"))
    )
    (net (code "178") (name "Net-(BUSAN-S)") (class "Default")
      (node (ref "BUS") (pin "9") (pinfunction "S_9") (pintype "passive"))
      (node (ref "U3") (pin "4") (pinfunction "A3_4") (pintype "bidirectional"))
    )
    (net (code "179") (name "Net-(BUSE-S)") (class "Default")
      (node (ref "BUS") (pin "13") (pinfunction "S_13") (pintype "passive"))
      (node (ref "U3") (pin "3") (pinfunction "A2_3") (pintype "bidirectional"))
    )
    (net (code "180") (name "Net-(BUSF-S)") (class "Default")
      (node (ref "BUS") (pin "14") (pinfunction "S_14") (pintype "passive"))
      (node (ref "U3") (pin "2") (pinfunction "A1_2") (pintype "bidirectional"))
    )
    (net (code "181") (name "Net-(BUSP-S)") (class "Default")
      (node (ref "BUS") (pin "23") (pinfunction "S_23") (pintype "passive"))
      (node (ref "U1") (pin "9") (pinfunction "A8_9") (pintype "bidirectional"))
    )
    (net (code "182") (name "Net-(BUSQ-S)") (class "Default")
      (node (ref "BUS") (pin "24") (pinfunction "S_24") (pintype "passive"))
      (node (ref "U1") (pin "8") (pinfunction "A7_8") (pintype "bidirectional"))
    )
    (net (code "183") (name "Net-(BUSR-S)") (class "Default")
      (node (ref "BUS") (pin "25") (pinfunction "S_25") (pintype "passive"))
      (node (ref "U1") (pin "7") (pinfunction "A6_7") (pintype "bidirectional"))
    )
    (net (code "184") (name "Net-(BUSS-S)") (class "Default")
      (node (ref "BUS") (pin "26") (pinfunction "S_26") (pintype "passive"))
      (node (ref "U1") (pin "6") (pinfunction "A5_6") (pintype "bidirectional"))
    )
    (net (code "185") (name "Net-(BUST-S)") (class "Default")
      (node (ref "BUS") (pin "27") (pinfunction "S_27") (pintype "passive"))
      (node (ref "U1") (pin "5") (pinfunction "A4_5") (pintype "bidirectional"))
    )
    (net (code "186") (name "Net-(BUSU-S)") (class "Default")
      (node (ref "BUS") (pin "28") (pinfunction "S_28") (pintype "passive"))
      (node (ref "U1") (pin "4") (pinfunction "A3_4") (pintype "bidirectional"))
    )
    (net (code "187") (name "Net-(BUSV-S)") (class "Default")
      (node (ref "BUS") (pin "29") (pinfunction "S_29") (pintype "passive"))
      (node (ref "U1") (pin "3") (pinfunction "A2_3") (pintype "bidirectional"))
    )
    (net (code "188") (name "Net-(BUSX-S)") (class "Default")
      (node (ref "BUS") (pin "30") (pinfunction "S_30") (pintype "passive"))
      (node (ref "U1") (pin "2") (pinfunction "A1_2") (pintype "bidirectional"))
    )
    (net (code "189") (name "Net-(SV1A-S)") (class "Default")
      (node (ref "R2") (pin "2") (pinfunction "2_2") (pintype "passive"))
      (node (ref "SV1") (pin "1") (pinfunction "S_1") (pintype "passive"))
    )
    (net (code "190") (name "Net-(SV1AA-S)") (class "Default")
      (node (ref "R50") (pin "2") (pinfunction "2_2") (pintype "passive"))
      (node (ref "SV1") (pin "33") (pinfunction "S_33") (pintype "passive"))
    )
    (net (code "191") (name "Net-(SV1AB-S)") (class "Default")
      (node (ref "R51") (pin "2") (pinfunction "2_2") (pintype "passive"))
      (node (ref "SV1") (pin "34") (pinfunction "S_34") (pintype "passive"))
    )
    (net (code "192") (name "Net-(SV1AC-S)") (class "Default")
      (node (ref "R52") (pin "2") (pinfunction "2_2") (pintype "passive"))
      (node (ref "SV1") (pin "35") (pinfunction "S_35") (pintype "passive"))
    )
    (net (code "193") (name "Net-(SV1AD-S)") (class "Default")
      (node (ref "R53") (pin "2") (pinfunction "2_2") (pintype "passive"))
      (node (ref "SV1") (pin "36") (pinfunction "S_36") (pintype "passive"))
    )
    (net (code "194") (name "Net-(SV1AE-S)") (class "Default")
      (node (ref "R54") (pin "2") (pinfunction "2_2") (pintype "passive"))
      (node (ref "SV1") (pin "37") (pinfunction "S_37") (pintype "passive"))
    )
    (net (code "195") (name "Net-(SV1AF-S)") (class "Default")
      (node (ref "R55") (pin "2") (pinfunction "2_2") (pintype "passive"))
      (node (ref "SV1") (pin "38") (pinfunction "S_38") (pintype "passive"))
    )
    (net (code "196") (name "Net-(SV1AG-S)") (class "Default")
      (node (ref "R56") (pin "2") (pinfunction "2_2") (pintype "passive"))
      (node (ref "SV1") (pin "39") (pinfunction "S_39") (pintype "passive"))
    )
    (net (code "197") (name "Net-(SV1AH-S)") (class "Default")
      (node (ref "R5") (pin "2") (pinfunction "2_2") (pintype "passive"))
      (node (ref "SV1") (pin "4") (pinfunction "S_4") (pintype "passive"))
    )
    (net (code "198") (name "Net-(SV1AI-S)") (class "Default")
      (node (ref "R57") (pin "2") (pinfunction "2_2") (pintype "passive"))
      (node (ref "SV1") (pin "40") (pinfunction "S_40") (pintype "passive"))
    )
    (net (code "199") (name "Net-(SV1AJ-S)") (class "Default")
      (node (ref "R6") (pin "2") (pinfunction "2_2") (pintype "passive"))
      (node (ref "SV1") (pin "5") (pinfunction "S_5") (pintype "passive"))
    )
    (net (code "200") (name "Net-(SV1AK-S)") (class "Default")
      (node (ref "R7") (pin "2") (pinfunction "2_2") (pintype "passive"))
      (node (ref "SV1") (pin "6") (pinfunction "S_6") (pintype "passive"))
    )
    (net (code "201") (name "Net-(SV1AL-S)") (class "Default")
      (node (ref "R8") (pin "2") (pinfunction "2_2") (pintype "passive"))
      (node (ref "SV1") (pin "7") (pinfunction "S_7") (pintype "passive"))
    )
    (net (code "202") (name "Net-(SV1AM-S)") (class "Default")
      (node (ref "R9") (pin "2") (pinfunction "2_2") (pintype "passive"))
      (node (ref "SV1") (pin "8") (pinfunction "S_8") (pintype "passive"))
    )
    (net (code "203") (name "Net-(SV1AN-S)") (class "Default")
      (node (ref "R10") (pin "2") (pinfunction "2_2") (pintype "passive"))
      (node (ref "SV1") (pin "9") (pinfunction "S_9") (pintype "passive"))
    )
    (net (code "204") (name "Net-(SV1B-S)") (class "Default")
      (node (ref "R11") (pin "2") (pinfunction "2_2") (pintype "passive"))
      (node (ref "SV1") (pin "10") (pinfunction "S_10") (pintype "passive"))
    )
    (net (code "205") (name "Net-(SV1C-S)") (class "Default")
      (node (ref "R12") (pin "2") (pinfunction "2_2") (pintype "passive"))
      (node (ref "SV1") (pin "11") (pinfunction "S_11") (pintype "passive"))
    )
    (net (code "206") (name "Net-(SV1D-S)") (class "Default")
      (node (ref "R13") (pin "2") (pinfunction "2_2") (pintype "passive"))
      (node (ref "SV1") (pin "12") (pinfunction "S_12") (pintype "passive"))
    )
    (net (code "207") (name "Net-(SV1E-S)") (class "Default")
      (node (ref "R14") (pin "2") (pinfunction "2_2") (pintype "passive"))
      (node (ref "SV1") (pin "13") (pinfunction "S_13") (pintype "passive"))
    )
    (net (code "208") (name "Net-(SV1F-S)") (class "Default")
      (node (ref "R15") (pin "2") (pinfunction "2_2") (pintype "passive"))
      (node (ref "SV1") (pin "14") (pinfunction "S_14") (pintype "passive"))
    )
    (net (code "209") (name "Net-(SV1G-S)") (class "Default")
      (node (ref "R16") (pin "2") (pinfunction "2_2") (pintype "passive"))
      (node (ref "SV1") (pin "15") (pinfunction "S_15") (pintype "passive"))
    )
    (net (code "210") (name "Net-(SV1H-S)") (class "Default")
      (node (ref "R17") (pin "2") (pinfunction "2_2") (pintype "passive"))
      (node (ref "SV1") (pin "16") (pinfunction "S_16") (pintype "passive"))
    )
    (net (code "211") (name "Net-(SV1I-S)") (class "Default")
      (node (ref "R18") (pin "2") (pinfunction "2_2") (pintype "passive"))
      (node (ref "SV1") (pin "17") (pinfunction "S_17") (pintype "passive"))
    )
    (net (code "212") (name "Net-(SV1J-S)") (class "Default")
      (node (ref "R19") (pin "2") (pinfunction "2_2") (pintype "passive"))
      (node (ref "SV1") (pin "18") (pinfunction "S_18") (pintype "passive"))
    )
    (net (code "213") (name "Net-(SV1K-S)") (class "Default")
      (node (ref "R20") (pin "2") (pinfunction "2_2") (pintype "passive"))
      (node (ref "SV1") (pin "19") (pinfunction "S_19") (pintype "passive"))
    )
    (net (code "214") (name "Net-(SV1L-S)") (class "Default")
      (node (ref "R3") (pin "2") (pinfunction "2_2") (pintype "passive"))
      (node (ref "SV1") (pin "2") (pinfunction "S_2") (pintype "passive"))
    )
    (net (code "215") (name "Net-(SV1M-S)") (class "Default")
      (node (ref "R21") (pin "2") (pinfunction "2_2") (pintype "passive"))
      (node (ref "SV1") (pin "20") (pinfunction "S_20") (pintype "passive"))
    )
    (net (code "216") (name "Net-(SV1N-S)") (class "Default")
      (node (ref "R22") (pin "2") (pinfunction "2_2") (pintype "passive"))
      (node (ref "SV1") (pin "21") (pinfunction "S_21") (pintype "passive"))
    )
    (net (code "217") (name "Net-(SV1O-S)") (class "Default")
      (node (ref "R23") (pin "2") (pinfunction "2_2") (pintype "passive"))
      (node (ref "SV1") (pin "22") (pinfunction "S_22") (pintype "passive"))
    )
    (net (code "218") (name "Net-(SV1P-S)") (class "Default")
      (node (ref "R24") (pin "2") (pinfunction "2_2") (pintype "passive"))
      (node (ref "SV1") (pin "23") (pinfunction "S_23") (pintype "passive"))
    )
    (net (code "219") (name "Net-(SV1Q-S)") (class "Default")
      (node (ref "R25") (pin "2") (pinfunction "2_2") (pintype "passive"))
      (node (ref "SV1") (pin "24") (pinfunction "S_24") (pintype "passive"))
    )
    (net (code "220") (name "Net-(SV1R-S)") (class "Default")
      (node (ref "R42") (pin "2") (pinfunction "2_2") (pintype "passive"))
      (node (ref "SV1") (pin "25") (pinfunction "S_25") (pintype "passive"))
    )
    (net (code "221") (name "Net-(SV1S-S)") (class "Default")
      (node (ref "R43") (pin "2") (pinfunction "2_2") (pintype "passive"))
      (node (ref "SV1") (pin "26") (pinfunction "S_26") (pintype "passive"))
    )
    (net (code "222") (name "Net-(SV1T-S)") (class "Default")
      (node (ref "R44") (pin "2") (pinfunction "2_2") (pintype "passive"))
      (node (ref "SV1") (pin "27") (pinfunction "S_27") (pintype "passive"))
    )
    (net (code "223") (name "Net-(SV1U-S)") (class "Default")
      (node (ref "R45") (pin "2") (pinfunction "2_2") (pintype "passive"))
      (node (ref "SV1") (pin "28") (pinfunction "S_28") (pintype "passive"))
    )
    (net (code "224") (name "Net-(SV1V-S)") (class "Default")
      (node (ref "R46") (pin "2") (pinfunction "2_2") (pintype "passive"))
      (node (ref "SV1") (pin "29") (pinfunction "S_29") (pintype "passive"))
    )
    (net (code "225") (name "Net-(SV1W-S)") (class "Default")
      (node (ref "R4") (pin "2") (pinfunction "2_2") (pintype "passive"))
      (node (ref "SV1") (pin "3") (pinfunction "S_3") (pintype "passive"))
    )
    (net (code "226") (name "Net-(SV1X-S)") (class "Default")
      (node (ref "R47") (pin "2") (pinfunction "2_2") (pintype "passive"))
      (node (ref "SV1") (pin "30") (pinfunction "S_30") (pintype "passive"))
    )
    (net (code "227") (name "Net-(SV1Y-S)") (class "Default")
      (node (ref "R48") (pin "2") (pinfunction "2_2") (pintype "passive"))
      (node (ref "SV1") (pin "31") (pinfunction "S_31") (pintype "passive"))
    )
    (net (code "228") (name "Net-(SV1Z-S)") (class "Default")
      (node (ref "R49") (pin "2") (pinfunction "2_2") (pintype "passive"))
      (node (ref "SV1") (pin "32") (pinfunction "S_32") (pintype "passive"))
    )
    (net (code "229") (name "Net-(SV2A-S)") (class "Default")
      (node (ref "R74") (pin "2") (pinfunction "2_2") (pintype "passive"))
      (node (ref "SV2") (pin "1") (pinfunction "S_1") (pintype "passive"))
    )
    (net (code "230") (name "Net-(SV2AA-S)") (class "Default")
      (node (ref "R122") (pin "2") (pinfunction "2_2") (pintype "passive"))
      (node (ref "SV2") (pin "33") (pinfunction "S_33") (pintype "passive"))
    )
    (net (code "231") (name "Net-(SV2AB-S)") (class "Default")
      (node (ref "R123") (pin "2") (pinfunction "2_2") (pintype "passive"))
      (node (ref "SV2") (pin "34") (pinfunction "S_34") (pintype "passive"))
    )
    (net (code "232") (name "Net-(SV2AC-S)") (class "Default")
      (node (ref "R124") (pin "2") (pinfunction "2_2") (pintype "passive"))
      (node (ref "SV2") (pin "35") (pinfunction "S_35") (pintype "passive"))
    )
    (net (code "233") (name "Net-(SV2AD-S)") (class "Default")
      (node (ref "R125") (pin "2") (pinfunction "2_2") (pintype "passive"))
      (node (ref "SV2") (pin "36") (pinfunction "S_36") (pintype "passive"))
    )
    (net (code "234") (name "Net-(SV2AE-S)") (class "Default")
      (node (ref "R126") (pin "2") (pinfunction "2_2") (pintype "passive"))
      (node (ref "SV2") (pin "37") (pinfunction "S_37") (pintype "passive"))
    )
    (net (code "235") (name "Net-(SV2AF-S)") (class "Default")
      (node (ref "R127") (pin "2") (pinfunction "2_2") (pintype "passive"))
      (node (ref "SV2") (pin "38") (pinfunction "S_38") (pintype "passive"))
    )
    (net (code "236") (name "Net-(SV2AG-S)") (class "Default")
      (node (ref "R128") (pin "2") (pinfunction "2_2") (pintype "passive"))
      (node (ref "SV2") (pin "39") (pinfunction "S_39") (pintype "passive"))
    )
    (net (code "237") (name "Net-(SV2AH-S)") (class "Default")
      (node (ref "R77") (pin "2") (pinfunction "2_2") (pintype "passive"))
      (node (ref "SV2") (pin "4") (pinfunction "S_4") (pintype "passive"))
    )
    (net (code "238") (name "Net-(SV2AI-S)") (class "Default")
      (node (ref "R129") (pin "2") (pinfunction "2_2") (pintype "passive"))
      (node (ref "SV2") (pin "40") (pinfunction "S_40") (pintype "passive"))
    )
    (net (code "239") (name "Net-(SV2AJ-S)") (class "Default")
      (node (ref "R78") (pin "2") (pinfunction "2_2") (pintype "passive"))
      (node (ref "SV2") (pin "5") (pinfunction "S_5") (pintype "passive"))
    )
    (net (code "240") (name "Net-(SV2AK-S)") (class "Default")
      (node (ref "R79") (pin "2") (pinfunction "2_2") (pintype "passive"))
      (node (ref "SV2") (pin "6") (pinfunction "S_6") (pintype "passive"))
    )
    (net (code "241") (name "Net-(SV2AL-S)") (class "Default")
      (node (ref "R80") (pin "2") (pinfunction "2_2") (pintype "passive"))
      (node (ref "SV2") (pin "7") (pinfunction "S_7") (pintype "passive"))
    )
    (net (code "242") (name "Net-(SV2AM-S)") (class "Default")
      (node (ref "R81") (pin "2") (pinfunction "2_2") (pintype "passive"))
      (node (ref "SV2") (pin "8") (pinfunction "S_8") (pintype "passive"))
    )
    (net (code "243") (name "Net-(SV2AN-S)") (class "Default")
      (node (ref "R82") (pin "2") (pinfunction "2_2") (pintype "passive"))
      (node (ref "SV2") (pin "9") (pinfunction "S_9") (pintype "passive"))
    )
    (net (code "244") (name "Net-(SV2B-S)") (class "Default")
      (node (ref "R83") (pin "2") (pinfunction "2_2") (pintype "passive"))
      (node (ref "SV2") (pin "10") (pinfunction "S_10") (pintype "passive"))
    )
    (net (code "245") (name "Net-(SV2C-S)") (class "Default")
      (node (ref "R84") (pin "2") (pinfunction "2_2") (pintype "passive"))
      (node (ref "SV2") (pin "11") (pinfunction "S_11") (pintype "passive"))
    )
    (net (code "246") (name "Net-(SV2D-S)") (class "Default")
      (node (ref "R85") (pin "2") (pinfunction "2_2") (pintype "passive"))
      (node (ref "SV2") (pin "12") (pinfunction "S_12") (pintype "passive"))
    )
    (net (code "247") (name "Net-(SV2E-S)") (class "Default")
      (node (ref "R86") (pin "2") (pinfunction "2_2") (pintype "passive"))
      (node (ref "SV2") (pin "13") (pinfunction "S_13") (pintype "passive"))
    )
    (net (code "248") (name "Net-(SV2F-S)") (class "Default")
      (node (ref "R87") (pin "2") (pinfunction "2_2") (pintype "passive"))
      (node (ref "SV2") (pin "14") (pinfunction "S_14") (pintype "passive"))
    )
    (net (code "249") (name "Net-(SV2G-S)") (class "Default")
      (node (ref "R88") (pin "2") (pinfunction "2_2") (pintype "passive"))
      (node (ref "SV2") (pin "15") (pinfunction "S_15") (pintype "passive"))
    )
    (net (code "250") (name "Net-(SV2H-S)") (class "Default")
      (node (ref "R89") (pin "2") (pinfunction "2_2") (pintype "passive"))
      (node (ref "SV2") (pin "16") (pinfunction "S_16") (pintype "passive"))
    )
    (net (code "251") (name "Net-(SV2I-S)") (class "Default")
      (node (ref "R106") (pin "2") (pinfunction "2_2") (pintype "passive"))
      (node (ref "SV2") (pin "17") (pinfunction "S_17") (pintype "passive"))
    )
    (net (code "252") (name "Net-(SV2J-S)") (class "Default")
      (node (ref "R107") (pin "2") (pinfunction "2_2") (pintype "passive"))
      (node (ref "SV2") (pin "18") (pinfunction "S_18") (pintype "passive"))
    )
    (net (code "253") (name "Net-(SV2K-S)") (class "Default")
      (node (ref "R108") (pin "2") (pinfunction "2_2") (pintype "passive"))
      (node (ref "SV2") (pin "19") (pinfunction "S_19") (pintype "passive"))
    )
    (net (code "254") (name "Net-(SV2L-S)") (class "Default")
      (node (ref "R75") (pin "2") (pinfunction "2_2") (pintype "passive"))
      (node (ref "SV2") (pin "2") (pinfunction "S_2") (pintype "passive"))
    )
    (net (code "255") (name "Net-(SV2M-S)") (class "Default")
      (node (ref "R109") (pin "2") (pinfunction "2_2") (pintype "passive"))
      (node (ref "SV2") (pin "20") (pinfunction "S_20") (pintype "passive"))
    )
    (net (code "256") (name "Net-(SV2N-S)") (class "Default")
      (node (ref "R110") (pin "2") (pinfunction "2_2") (pintype "passive"))
      (node (ref "SV2") (pin "21") (pinfunction "S_21") (pintype "passive"))
    )
    (net (code "257") (name "Net-(SV2O-S)") (class "Default")
      (node (ref "R111") (pin "2") (pinfunction "2_2") (pintype "passive"))
      (node (ref "SV2") (pin "22") (pinfunction "S_22") (pintype "passive"))
    )
    (net (code "258") (name "Net-(SV2P-S)") (class "Default")
      (node (ref "R112") (pin "2") (pinfunction "2_2") (pintype "passive"))
      (node (ref "SV2") (pin "23") (pinfunction "S_23") (pintype "passive"))
    )
    (net (code "259") (name "Net-(SV2Q-S)") (class "Default")
      (node (ref "R113") (pin "2") (pinfunction "2_2") (pintype "passive"))
      (node (ref "SV2") (pin "24") (pinfunction "S_24") (pintype "passive"))
    )
    (net (code "260") (name "Net-(SV2R-S)") (class "Default")
      (node (ref "R114") (pin "2") (pinfunction "2_2") (pintype "passive"))
      (node (ref "SV2") (pin "25") (pinfunction "S_25") (pintype "passive"))
    )
    (net (code "261") (name "Net-(SV2S-S)") (class "Default")
      (node (ref "R115") (pin "2") (pinfunction "2_2") (pintype "passive"))
      (node (ref "SV2") (pin "26") (pinfunction "S_26") (pintype "passive"))
    )
    (net (code "262") (name "Net-(SV2T-S)") (class "Default")
      (node (ref "R116") (pin "2") (pinfunction "2_2") (pintype "passive"))
      (node (ref "SV2") (pin "27") (pinfunction "S_27") (pintype "passive"))
    )
    (net (code "263") (name "Net-(SV2U-S)") (class "Default")
      (node (ref "R117") (pin "2") (pinfunction "2_2") (pintype "passive"))
      (node (ref "SV2") (pin "28") (pinfunction "S_28") (pintype "passive"))
    )
    (net (code "264") (name "Net-(SV2V-S)") (class "Default")
      (node (ref "R118") (pin "2") (pinfunction "2_2") (pintype "passive"))
      (node (ref "SV2") (pin "29") (pinfunction "S_29") (pintype "passive"))
    )
    (net (code "265") (name "Net-(SV2W-S)") (class "Default")
      (node (ref "R76") (pin "2") (pinfunction "2_2") (pintype "passive"))
      (node (ref "SV2") (pin "3") (pinfunction "S_3") (pintype "passive"))
    )
    (net (code "266") (name "Net-(SV2X-S)") (class "Default")
      (node (ref "R119") (pin "2") (pinfunction "2_2") (pintype "passive"))
      (node (ref "SV2") (pin "30") (pinfunction "S_30") (pintype "passive"))
    )
    (net (code "267") (name "Net-(SV2Y-S)") (class "Default")
      (node (ref "R120") (pin "2") (pinfunction "2_2") (pintype "passive"))
      (node (ref "SV2") (pin "31") (pinfunction "S_31") (pintype "passive"))
    )
    (net (code "268") (name "Net-(SV2Z-S)") (class "Default")
      (node (ref "R121") (pin "2") (pinfunction "2_2") (pintype "passive"))
      (node (ref "SV2") (pin "32") (pinfunction "S_32") (pintype "passive"))
    )
    (net (code "269") (name "Net-(SV3A-S)") (class "Default")
      (node (ref "R26") (pin "2") (pinfunction "2_2") (pintype "passive"))
      (node (ref "SV3") (pin "1") (pinfunction "S_1") (pintype "passive"))
    )
    (net (code "270") (name "Net-(SV3AA-S)") (class "Default")
      (node (ref "R66") (pin "2") (pinfunction "2_2") (pintype "passive"))
      (node (ref "SV3") (pin "33") (pinfunction "S_33") (pintype "passive"))
    )
    (net (code "271") (name "Net-(SV3AB-S)") (class "Default")
      (node (ref "R67") (pin "2") (pinfunction "2_2") (pintype "passive"))
      (node (ref "SV3") (pin "34") (pinfunction "S_34") (pintype "passive"))
    )
    (net (code "272") (name "Net-(SV3AC-S)") (class "Default")
      (node (ref "R68") (pin "2") (pinfunction "2_2") (pintype "passive"))
      (node (ref "SV3") (pin "35") (pinfunction "S_35") (pintype "passive"))
    )
    (net (code "273") (name "Net-(SV3AD-S)") (class "Default")
      (node (ref "R69") (pin "2") (pinfunction "2_2") (pintype "passive"))
      (node (ref "SV3") (pin "36") (pinfunction "S_36") (pintype "passive"))
    )
    (net (code "274") (name "Net-(SV3AE-S)") (class "Default")
      (node (ref "R70") (pin "2") (pinfunction "2_2") (pintype "passive"))
      (node (ref "SV3") (pin "37") (pinfunction "S_37") (pintype "passive"))
    )
    (net (code "275") (name "Net-(SV3AF-S)") (class "Default")
      (node (ref "R71") (pin "2") (pinfunction "2_2") (pintype "passive"))
      (node (ref "SV3") (pin "38") (pinfunction "S_38") (pintype "passive"))
    )
    (net (code "276") (name "Net-(SV3AG-S)") (class "Default")
      (node (ref "R72") (pin "2") (pinfunction "2_2") (pintype "passive"))
      (node (ref "SV3") (pin "39") (pinfunction "S_39") (pintype "passive"))
    )
    (net (code "277") (name "Net-(SV3AH-S)") (class "Default")
      (node (ref "R29") (pin "2") (pinfunction "2_2") (pintype "passive"))
      (node (ref "SV3") (pin "4") (pinfunction "S_4") (pintype "passive"))
    )
    (net (code "278") (name "Net-(SV3AI-S)") (class "Default")
      (node (ref "R73") (pin "2") (pinfunction "2_2") (pintype "passive"))
      (node (ref "SV3") (pin "40") (pinfunction "S_40") (pintype "passive"))
    )
    (net (code "279") (name "Net-(SV3AJ-S)") (class "Default")
      (node (ref "R30") (pin "2") (pinfunction "2_2") (pintype "passive"))
      (node (ref "SV3") (pin "5") (pinfunction "S_5") (pintype "passive"))
    )
    (net (code "280") (name "Net-(SV3AK-S)") (class "Default")
      (node (ref "R31") (pin "2") (pinfunction "2_2") (pintype "passive"))
      (node (ref "SV3") (pin "6") (pinfunction "S_6") (pintype "passive"))
    )
    (net (code "281") (name "Net-(SV3AL-S)") (class "Default")
      (node (ref "R32") (pin "2") (pinfunction "2_2") (pintype "passive"))
      (node (ref "SV3") (pin "7") (pinfunction "S_7") (pintype "passive"))
    )
    (net (code "282") (name "Net-(SV3AM-S)") (class "Default")
      (node (ref "R33") (pin "2") (pinfunction "2_2") (pintype "passive"))
      (node (ref "SV3") (pin "8") (pinfunction "S_8") (pintype "passive"))
    )
    (net (code "283") (name "Net-(SV3AN-S)") (class "Default")
      (node (ref "R34") (pin "2") (pinfunction "2_2") (pintype "passive"))
      (node (ref "SV3") (pin "9") (pinfunction "S_9") (pintype "passive"))
    )
    (net (code "284") (name "Net-(SV3B-S)") (class "Default")
      (node (ref "R35") (pin "2") (pinfunction "2_2") (pintype "passive"))
      (node (ref "SV3") (pin "10") (pinfunction "S_10") (pintype "passive"))
    )
    (net (code "285") (name "Net-(SV3C-S)") (class "Default")
      (node (ref "R36") (pin "2") (pinfunction "2_2") (pintype "passive"))
      (node (ref "SV3") (pin "11") (pinfunction "S_11") (pintype "passive"))
    )
    (net (code "286") (name "Net-(SV3D-S)") (class "Default")
      (node (ref "R37") (pin "2") (pinfunction "2_2") (pintype "passive"))
      (node (ref "SV3") (pin "12") (pinfunction "S_12") (pintype "passive"))
    )
    (net (code "287") (name "Net-(SV3E-S)") (class "Default")
      (node (ref "R38") (pin "2") (pinfunction "2_2") (pintype "passive"))
      (node (ref "SV3") (pin "13") (pinfunction "S_13") (pintype "passive"))
    )
    (net (code "288") (name "Net-(SV3F-S)") (class "Default")
      (node (ref "R39") (pin "2") (pinfunction "2_2") (pintype "passive"))
      (node (ref "SV3") (pin "14") (pinfunction "S_14") (pintype "passive"))
    )
    (net (code "289") (name "Net-(SV3G-S)") (class "Default")
      (node (ref "R40") (pin "2") (pinfunction "2_2") (pintype "passive"))
      (node (ref "SV3") (pin "15") (pinfunction "S_15") (pintype "passive"))
    )
    (net (code "290") (name "Net-(SV3H-S)") (class "Default")
      (node (ref "R41") (pin "2") (pinfunction "2_2") (pintype "passive"))
      (node (ref "SV3") (pin "16") (pinfunction "S_16") (pintype "passive"))
    )
    (net (code "291") (name "Net-(SV3L-S)") (class "Default")
      (node (ref "R27") (pin "2") (pinfunction "2_2") (pintype "passive"))
      (node (ref "SV3") (pin "2") (pinfunction "S_2") (pintype "passive"))
    )
    (net (code "292") (name "Net-(SV3R-S)") (class "Default")
      (node (ref "R58") (pin "2") (pinfunction "2_2") (pintype "passive"))
      (node (ref "SV3") (pin "25") (pinfunction "S_25") (pintype "passive"))
    )
    (net (code "293") (name "Net-(SV3S-S)") (class "Default")
      (node (ref "R59") (pin "2") (pinfunction "2_2") (pintype "passive"))
      (node (ref "SV3") (pin "26") (pinfunction "S_26") (pintype "passive"))
    )
    (net (code "294") (name "Net-(SV3T-S)") (class "Default")
      (node (ref "R60") (pin "2") (pinfunction "2_2") (pintype "passive"))
      (node (ref "SV3") (pin "27") (pinfunction "S_27") (pintype "passive"))
    )
    (net (code "295") (name "Net-(SV3U-S)") (class "Default")
      (node (ref "R61") (pin "2") (pinfunction "2_2") (pintype "passive"))
      (node (ref "SV3") (pin "28") (pinfunction "S_28") (pintype "passive"))
    )
    (net (code "296") (name "Net-(SV3V-S)") (class "Default")
      (node (ref "R62") (pin "2") (pinfunction "2_2") (pintype "passive"))
      (node (ref "SV3") (pin "29") (pinfunction "S_29") (pintype "passive"))
    )
    (net (code "297") (name "Net-(SV3W-S)") (class "Default")
      (node (ref "R28") (pin "2") (pinfunction "2_2") (pintype "passive"))
      (node (ref "SV3") (pin "3") (pinfunction "S_3") (pintype "passive"))
    )
    (net (code "298") (name "Net-(SV3X-S)") (class "Default")
      (node (ref "R63") (pin "2") (pinfunction "2_2") (pintype "passive"))
      (node (ref "SV3") (pin "30") (pinfunction "S_30") (pintype "passive"))
    )
    (net (code "299") (name "Net-(SV3Y-S)") (class "Default")
      (node (ref "R64") (pin "2") (pinfunction "2_2") (pintype "passive"))
      (node (ref "SV3") (pin "31") (pinfunction "S_31") (pintype "passive"))
    )
    (net (code "300") (name "Net-(SV3Z-S)") (class "Default")
      (node (ref "R65") (pin "2") (pinfunction "2_2") (pintype "passive"))
      (node (ref "SV3") (pin "32") (pinfunction "S_32") (pintype "passive"))
    )
    (net (code "301") (name "Net-(SV4A-S)") (class "Default")
      (node (ref "R90") (pin "2") (pinfunction "2_2") (pintype "passive"))
      (node (ref "SV4") (pin "1") (pinfunction "S_1") (pintype "passive"))
    )
    (net (code "302") (name "Net-(SV4AH-S)") (class "Default")
      (node (ref "R93") (pin "2") (pinfunction "2_2") (pintype "passive"))
      (node (ref "SV4") (pin "4") (pinfunction "S_4") (pintype "passive"))
    )
    (net (code "303") (name "Net-(SV4AJ-S)") (class "Default")
      (node (ref "R94") (pin "2") (pinfunction "2_2") (pintype "passive"))
      (node (ref "SV4") (pin "5") (pinfunction "S_5") (pintype "passive"))
    )
    (net (code "304") (name "Net-(SV4AK-S)") (class "Default")
      (node (ref "R95") (pin "2") (pinfunction "2_2") (pintype "passive"))
      (node (ref "SV4") (pin "6") (pinfunction "S_6") (pintype "passive"))
    )
    (net (code "305") (name "Net-(SV4AL-S)") (class "Default")
      (node (ref "R96") (pin "2") (pinfunction "2_2") (pintype "passive"))
      (node (ref "SV4") (pin "7") (pinfunction "S_7") (pintype "passive"))
    )
    (net (code "306") (name "Net-(SV4AM-S)") (class "Default")
      (node (ref "R97") (pin "2") (pinfunction "2_2") (pintype "passive"))
      (node (ref "SV4") (pin "8") (pinfunction "S_8") (pintype "passive"))
    )
    (net (code "307") (name "Net-(SV4AN-S)") (class "Default")
      (node (ref "R98") (pin "2") (pinfunction "2_2") (pintype "passive"))
      (node (ref "SV4") (pin "9") (pinfunction "S_9") (pintype "passive"))
    )
    (net (code "308") (name "Net-(SV4B-S)") (class "Default")
      (node (ref "R99") (pin "2") (pinfunction "2_2") (pintype "passive"))
      (node (ref "SV4") (pin "10") (pinfunction "S_10") (pintype "passive"))
    )
    (net (code "309") (name "Net-(SV4C-S)") (class "Default")
      (node (ref "R100") (pin "2") (pinfunction "2_2") (pintype "passive"))
      (node (ref "SV4") (pin "11") (pinfunction "S_11") (pintype "passive"))
    )
    (net (code "310") (name "Net-(SV4D-S)") (class "Default")
      (node (ref "R101") (pin "2") (pinfunction "2_2") (pintype "passive"))
      (node (ref "SV4") (pin "12") (pinfunction "S_12") (pintype "passive"))
    )
    (net (code "311") (name "Net-(SV4E-S)") (class "Default")
      (node (ref "R102") (pin "2") (pinfunction "2_2") (pintype "passive"))
      (node (ref "SV4") (pin "13") (pinfunction "S_13") (pintype "passive"))
    )
    (net (code "312") (name "Net-(SV4F-S)") (class "Default")
      (node (ref "R103") (pin "2") (pinfunction "2_2") (pintype "passive"))
      (node (ref "SV4") (pin "14") (pinfunction "S_14") (pintype "passive"))
    )
    (net (code "313") (name "Net-(SV4G-S)") (class "Default")
      (node (ref "R104") (pin "2") (pinfunction "2_2") (pintype "passive"))
      (node (ref "SV4") (pin "15") (pinfunction "S_15") (pintype "passive"))
    )
    (net (code "314") (name "Net-(SV4H-S)") (class "Default")
      (node (ref "R105") (pin "2") (pinfunction "2_2") (pintype "passive"))
      (node (ref "SV4") (pin "16") (pinfunction "S_16") (pintype "passive"))
    )
    (net (code "315") (name "Net-(SV4I-S)") (class "Default")
      (node (ref "R130") (pin "2") (pinfunction "2_2") (pintype "passive"))
      (node (ref "SV4") (pin "17") (pinfunction "S_17") (pintype "passive"))
    )
    (net (code "316") (name "Net-(SV4J-S)") (class "Default")
      (node (ref "R131") (pin "2") (pinfunction "2_2") (pintype "passive"))
      (node (ref "SV4") (pin "18") (pinfunction "S_18") (pintype "passive"))
    )
    (net (code "317") (name "Net-(SV4K-S)") (class "Default")
      (node (ref "R132") (pin "2") (pinfunction "2_2") (pintype "passive"))
      (node (ref "SV4") (pin "19") (pinfunction "S_19") (pintype "passive"))
    )
    (net (code "318") (name "Net-(SV4L-S)") (class "Default")
      (node (ref "R91") (pin "2") (pinfunction "2_2") (pintype "passive"))
      (node (ref "SV4") (pin "2") (pinfunction "S_2") (pintype "passive"))
    )
    (net (code "319") (name "Net-(SV4M-S)") (class "Default")
      (node (ref "R133") (pin "2") (pinfunction "2_2") (pintype "passive"))
      (node (ref "SV4") (pin "20") (pinfunction "S_20") (pintype "passive"))
    )
    (net (code "320") (name "Net-(SV4N-S)") (class "Default")
      (node (ref "R134") (pin "2") (pinfunction "2_2") (pintype "passive"))
      (node (ref "SV4") (pin "21") (pinfunction "S_21") (pintype "passive"))
    )
    (net (code "321") (name "Net-(SV4O-S)") (class "Default")
      (node (ref "R135") (pin "2") (pinfunction "2_2") (pintype "passive"))
      (node (ref "SV4") (pin "22") (pinfunction "S_22") (pintype "passive"))
    )
    (net (code "322") (name "Net-(SV4P-S)") (class "Default")
      (node (ref "R136") (pin "2") (pinfunction "2_2") (pintype "passive"))
      (node (ref "SV4") (pin "23") (pinfunction "S_23") (pintype "passive"))
    )
    (net (code "323") (name "Net-(SV4Q-S)") (class "Default")
      (node (ref "R137") (pin "2") (pinfunction "2_2") (pintype "passive"))
      (node (ref "SV4") (pin "24") (pinfunction "S_24") (pintype "passive"))
    )
    (net (code "324") (name "Net-(SV4W-S)") (class "Default")
      (node (ref "R92") (pin "2") (pinfunction "2_2") (pintype "passive"))
      (node (ref "SV4") (pin "3") (pinfunction "S_3") (pintype "passive"))
    )
    (net (code "325") (name "Net-(U6A-O)") (class "Default")
      (node (ref "U6") (pin "2") (pinfunction "O_2") (pintype "output"))
      (node (ref "U8") (pin "10") (pinfunction "I1_10") (pintype "input"))
    )
    (net (code "326") (name "Net-(U6B-O)") (class "Default")
      (node (ref "U6") (pin "4") (pinfunction "O_4") (pintype "output"))
      (node (ref "U8") (pin "12") (pinfunction "I0_12") (pintype "input"))
    )
    (net (code "327") (name "Net-(U6D-I)") (class "Default")
      (node (ref "U6") (pin "9") (pinfunction "I_9") (pintype "input"))
      (node (ref "U8") (pin "8") (pinfunction "O_8") (pintype "output"))
    )
    (net (code "328") (name "Net-(U6D-O)") (class "Default")
      (node (ref "U6") (pin "8") (pinfunction "O_8") (pintype "output"))
      (node (ref "U8") (pin "2") (pinfunction "I1_2") (pintype "input"))
    )
    (net (code "329") (name "Net-(U7A-CLR)") (class "Default")
      (node (ref "U7") (pin "1") (pinfunction "CLR_1") (pintype "input"))
      (node (ref "U8") (pin "3") (pinfunction "O_3") (pintype "output"))
    )
    (net (code "330") (name "Net-(U7A-Q)") (class "Default")
      (node (ref "U7") (pin "5") (pinfunction "Q_5") (pintype "output"))
      (node (ref "U8") (pin "5") (pinfunction "I1_5") (pintype "input"))
    )
    (net (code "331") (name "Net-(U7A-~{Q})") (class "Default")
      (node (ref "U7") (pin "6") (pinfunction "~{Q}_6") (pintype "output"))
      (node (ref "U9") (pin "2") (pinfunction "CLR_2") (pintype "input"))
    )
    (net (code "332") (name "Net-(U8C-I0)") (class "Default")
      (node (ref "U8") (pin "9") (pinfunction "I0_9") (pintype "input"))
      (node (ref "U9") (pin "6") (pinfunction "QD_6") (pintype "output"))
    )
    (net (code "333") (name "Net-(U10A-O)") (class "Default")
      (node (ref "U10") (pin "3") (pinfunction "O_3") (pintype "output"))
      (node (ref "U4") (pin "1") (pinfunction "G_1") (pintype "input"))
      (node (ref "U5") (pin "1") (pinfunction "G_1") (pintype "input"))
    )
    (net (code "334") (name "Net-(U10B-I0)") (class "Default")
      (node (ref "U10") (pin "4") (pinfunction "I0_4") (pintype "input"))
      (node (ref "U8") (pin "11") (pinfunction "O_11") (pintype "output"))
    )
    (net (code "335") (name "Net-(U10B-I1)") (class "Default")
      (node (ref "U10") (pin "5") (pinfunction "I1_5") (pintype "input"))
      (node (ref "U15") (pin "11") (pinfunction "SCK_11") (pintype "input"))
      (node (ref "U16") (pin "11") (pinfunction "SCK_11") (pintype "input"))
      (node (ref "U17") (pin "11") (pinfunction "SCK_11") (pintype "input"))
      (node (ref "U18") (pin "11") (pinfunction "SCK_11") (pintype "input"))
      (node (ref "U19") (pin "11") (pinfunction "SCK_11") (pintype "input"))
      (node (ref "U20") (pin "11") (pinfunction "SCK_11") (pintype "input"))
      (node (ref "U21") (pin "11") (pinfunction "SCK_11") (pintype "input"))
      (node (ref "U22") (pin "11") (pinfunction "SCK_11") (pintype "input"))
      (node (ref "U23") (pin "11") (pinfunction "SCK_11") (pintype "input"))
      (node (ref "U24") (pin "11") (pinfunction "SCK_11") (pintype "input"))
      (node (ref "U25") (pin "11") (pinfunction "SCK_11") (pintype "input"))
      (node (ref "U26") (pin "11") (pinfunction "SCK_11") (pintype "input"))
      (node (ref "U27") (pin "11") (pinfunction "SCK_11") (pintype "input"))
      (node (ref "U28") (pin "11") (pinfunction "SCK_11") (pintype "input"))
      (node (ref "U29") (pin "11") (pinfunction "SCK_11") (pintype "input"))
      (node (ref "U30") (pin "11") (pinfunction "SCK_11") (pintype "input"))
      (node (ref "U31") (pin "11") (pinfunction "SCK_11") (pintype "input"))
      (node (ref "U6") (pin "1") (pinfunction "I_1") (pintype "input"))
      (node (ref "U8") (pin "6") (pinfunction "O_6") (pintype "output"))
      (node (ref "U9") (pin "1") (pinfunction "A_1") (pintype "input"))
    )
    (net (code "336") (name "Net-(U10B-O)") (class "Default")
      (node (ref "U10") (pin "6") (pinfunction "O_6") (pintype "output"))
      (node (ref "U11") (pin "7") (pinfunction "CLK_7") (pintype "input"))
    )
    (net (code "337") (name "Net-(U11A-QH)") (class "Default")
      (node (ref "U11") (pin "13") (pinfunction "QH_13") (pintype "output"))
      (node (ref "U15") (pin "14") (pinfunction "SER_14") (pintype "input"))
    )
    (net (code "338") (name "Net-(U11A-SH{slash}~{LD})") (class "Default")
      (node (ref "U11") (pin "15") (pinfunction "SH/~{LD}_15") (pintype "input"))
      (node (ref "U4") (pin "19") (pinfunction "P=Q_19") (pintype "output"))
      (node (ref "U6") (pin "3") (pinfunction "I_3") (pintype "input"))
      (node (ref "U7") (pin "3") (pinfunction "CLK_3") (pintype "input"))
    )
    (net (code "339") (name "Net-(U12A-I1)") (class "Default")
      (node (ref "U12") (pin "2") (pinfunction "I1_2") (pintype "input"))
      (node (ref "U12") (pin "5") (pinfunction "I1_5") (pintype "input"))
      (node (ref "U5") (pin "19") (pinfunction "P=Q_19") (pintype "output"))
    )
    (net (code "340") (name "Net-(U12A-O)") (class "Default")
      (node (ref "U12") (pin "3") (pinfunction "O_3") (pintype "output"))
      (node (ref "U15") (pin "12") (pinfunction "RCK_12") (pintype "input"))
      (node (ref "U16") (pin "12") (pinfunction "RCK_12") (pintype "input"))
      (node (ref "U17") (pin "12") (pinfunction "RCK_12") (pintype "input"))
      (node (ref "U18") (pin "12") (pinfunction "RCK_12") (pintype "input"))
      (node (ref "U19") (pin "12") (pinfunction "RCK_12") (pintype "input"))
      (node (ref "U20") (pin "12") (pinfunction "RCK_12") (pintype "input"))
      (node (ref "U21") (pin "12") (pinfunction "RCK_12") (pintype "input"))
      (node (ref "U22") (pin "12") (pinfunction "RCK_12") (pintype "input"))
      (node (ref "U23") (pin "12") (pinfunction "RCK_12") (pintype "input"))
      (node (ref "U24") (pin "12") (pinfunction "RCK_12") (pintype "input"))
      (node (ref "U25") (pin "12") (pinfunction "RCK_12") (pintype "input"))
      (node (ref "U26") (pin "12") (pinfunction "RCK_12") (pintype "input"))
      (node (ref "U27") (pin "12") (pinfunction "RCK_12") (pintype "input"))
      (node (ref "U28") (pin "12") (pinfunction "RCK_12") (pintype "input"))
      (node (ref "U29") (pin "12") (pinfunction "RCK_12") (pintype "input"))
      (node (ref "U30") (pin "12") (pinfunction "RCK_12") (pintype "input"))
      (node (ref "U31") (pin "12") (pinfunction "RCK_12") (pintype "input"))
    )
    (net (code "341") (name "Net-(U12B-O)") (class "Default")
      (node (ref "U12") (pin "6") (pinfunction "O_6") (pintype "output"))
      (node (ref "U6") (pin "5") (pinfunction "I_5") (pintype "input"))
    )
    (net (code "342") (name "Net-(U13A-1Q)") (class "Default")
      (node (ref "U13") (pin "19") (pinfunction "1Q_19") (pintype "tri_state"))
      (node (ref "U14") (pin "1") (pinfunction "A_1") (pintype "input"))
    )
    (net (code "343") (name "Net-(U13A-2Q)") (class "Default")
      (node (ref "U13") (pin "18") (pinfunction "2Q_18") (pintype "tri_state"))
      (node (ref "U14") (pin "2") (pinfunction "B_2") (pintype "input"))
    )
    (net (code "344") (name "Net-(U13A-C)") (class "Default")
      (node (ref "U13") (pin "11") (pinfunction "C_11") (pintype "input"))
      (node (ref "U6") (pin "6") (pinfunction "O_6") (pintype "output"))
    )
    (net (code "345") (name "Net-(U15A-QH*)") (class "Default")
      (node (ref "U15") (pin "9") (pinfunction "QH*_9") (pintype "tri_state"))
      (node (ref "U16") (pin "14") (pinfunction "SER_14") (pintype "input"))
    )
    (net (code "346") (name "Net-(U16A-QH*)") (class "Default")
      (node (ref "U16") (pin "9") (pinfunction "QH*_9") (pintype "tri_state"))
      (node (ref "U17") (pin "14") (pinfunction "SER_14") (pintype "input"))
    )
    (net (code "347") (name "Net-(U17A-QH*)") (class "Default")
      (node (ref "U17") (pin "9") (pinfunction "QH*_9") (pintype "tri_state"))
      (node (ref "U18") (pin "14") (pinfunction "SER_14") (pintype "input"))
    )
    (net (code "348") (name "Net-(U18A-QH*)") (class "Default")
      (node (ref "U18") (pin "9") (pinfunction "QH*_9") (pintype "tri_state"))
      (node (ref "U19") (pin "14") (pinfunction "SER_14") (pintype "input"))
    )
    (net (code "349") (name "Net-(U19A-QH*)") (class "Default")
      (node (ref "U19") (pin "9") (pinfunction "QH*_9") (pintype "tri_state"))
      (node (ref "U20") (pin "14") (pinfunction "SER_14") (pintype "input"))
    )
    (net (code "350") (name "Net-(U20A-QH*)") (class "Default")
      (node (ref "U20") (pin "9") (pinfunction "QH*_9") (pintype "tri_state"))
      (node (ref "U21") (pin "14") (pinfunction "SER_14") (pintype "input"))
    )
    (net (code "351") (name "Net-(U21A-QH*)") (class "Default")
      (node (ref "U21") (pin "9") (pinfunction "QH*_9") (pintype "tri_state"))
      (node (ref "U22") (pin "14") (pinfunction "SER_14") (pintype "input"))
    )
    (net (code "352") (name "Net-(U22A-QH*)") (class "Default")
      (node (ref "U22") (pin "9") (pinfunction "QH*_9") (pintype "tri_state"))
      (node (ref "U23") (pin "14") (pinfunction "SER_14") (pintype "input"))
    )
    (net (code "353") (name "Net-(U23A-QH*)") (class "Default")
      (node (ref "U23") (pin "9") (pinfunction "QH*_9") (pintype "tri_state"))
      (node (ref "U24") (pin "14") (pinfunction "SER_14") (pintype "input"))
    )
    (net (code "354") (name "Net-(U24A-QH*)") (class "Default")
      (node (ref "U24") (pin "9") (pinfunction "QH*_9") (pintype "tri_state"))
      (node (ref "U25") (pin "14") (pinfunction "SER_14") (pintype "input"))
    )
    (net (code "355") (name "Net-(U25A-QH*)") (class "Default")
      (node (ref "U25") (pin "9") (pinfunction "QH*_9") (pintype "tri_state"))
      (node (ref "U26") (pin "14") (pinfunction "SER_14") (pintype "input"))
    )
    (net (code "356") (name "Net-(U26A-QH*)") (class "Default")
      (node (ref "U26") (pin "9") (pinfunction "QH*_9") (pintype "tri_state"))
      (node (ref "U27") (pin "14") (pinfunction "SER_14") (pintype "input"))
    )
    (net (code "357") (name "Net-(U27A-QH*)") (class "Default")
      (node (ref "U27") (pin "9") (pinfunction "QH*_9") (pintype "tri_state"))
      (node (ref "U28") (pin "14") (pinfunction "SER_14") (pintype "input"))
    )
    (net (code "358") (name "Net-(U28A-QH*)") (class "Default")
      (node (ref "U28") (pin "9") (pinfunction "QH*_9") (pintype "tri_state"))
      (node (ref "U29") (pin "14") (pinfunction "SER_14") (pintype "input"))
    )
    (net (code "359") (name "Net-(U29A-QH*)") (class "Default")
      (node (ref "U29") (pin "9") (pinfunction "QH*_9") (pintype "tri_state"))
      (node (ref "U30") (pin "14") (pinfunction "SER_14") (pintype "input"))
    )
    (net (code "360") (name "Net-(U30A-QH*)") (class "Default")
      (node (ref "U30") (pin "9") (pinfunction "QH*_9") (pintype "tri_state"))
      (node (ref "U31") (pin "14") (pinfunction "SER_14") (pintype "input"))
    )
    (net (code "361") (name "unconnected-(BUSG-S-Pad15)") (class "Default")
      (node (ref "BUS") (pin "15") (pinfunction "S_15") (pintype "passive"))
    )
    (net (code "362") (name "unconnected-(BUSH-S-Pad16)") (class "Default")
      (node (ref "BUS") (pin "16") (pinfunction "S_16") (pintype "passive"))
    )
    (net (code "363") (name "unconnected-(BUSI-S-Pad17)") (class "Default")
      (node (ref "BUS") (pin "17") (pinfunction "S_17") (pintype "passive"))
    )
    (net (code "364") (name "unconnected-(BUSJ-S-Pad18)") (class "Default")
      (node (ref "BUS") (pin "18") (pinfunction "S_18") (pintype "passive"))
    )
    (net (code "365") (name "unconnected-(BUSK-S-Pad19)") (class "Default")
      (node (ref "BUS") (pin "19") (pinfunction "S_19") (pintype "passive"))
    )
    (net (code "366") (name "unconnected-(BUSM-S-Pad20)") (class "Default")
      (node (ref "BUS") (pin "20") (pinfunction "S_20") (pintype "passive"))
    )
    (net (code "367") (name "unconnected-(BUSN-S-Pad21)") (class "Default")
      (node (ref "BUS") (pin "21") (pinfunction "S_21") (pintype "passive"))
    )
    (net (code "368") (name "unconnected-(BUSO-S-Pad22)") (class "Default")
      (node (ref "BUS") (pin "22") (pinfunction "S_22") (pintype "passive"))
    )
    (net (code "369") (name "unconnected-(SV3I-S-Pad17)") (class "Default")
      (node (ref "SV3") (pin "17") (pinfunction "S_17") (pintype "passive"))
    )
    (net (code "370") (name "unconnected-(SV3J-S-Pad18)") (class "Default")
      (node (ref "SV3") (pin "18") (pinfunction "S_18") (pintype "passive"))
    )
    (net (code "371") (name "unconnected-(SV3K-S-Pad19)") (class "Default")
      (node (ref "SV3") (pin "19") (pinfunction "S_19") (pintype "passive"))
    )
    (net (code "372") (name "unconnected-(SV3M-S-Pad20)") (class "Default")
      (node (ref "SV3") (pin "20") (pinfunction "S_20") (pintype "passive"))
    )
    (net (code "373") (name "unconnected-(SV3N-S-Pad21)") (class "Default")
      (node (ref "SV3") (pin "21") (pinfunction "S_21") (pintype "passive"))
    )
    (net (code "374") (name "unconnected-(SV3O-S-Pad22)") (class "Default")
      (node (ref "SV3") (pin "22") (pinfunction "S_22") (pintype "passive"))
    )
    (net (code "375") (name "unconnected-(SV3P-S-Pad23)") (class "Default")
      (node (ref "SV3") (pin "23") (pinfunction "S_23") (pintype "passive"))
    )
    (net (code "376") (name "unconnected-(SV3Q-S-Pad24)") (class "Default")
      (node (ref "SV3") (pin "24") (pinfunction "S_24") (pintype "passive"))
    )
    (net (code "377") (name "unconnected-(SV4AA-S-Pad33)") (class "Default")
      (node (ref "SV4") (pin "33") (pinfunction "S_33") (pintype "passive"))
    )
    (net (code "378") (name "unconnected-(SV4R-S-Pad25)") (class "Default")
      (node (ref "SV4") (pin "25") (pinfunction "S_25") (pintype "passive"))
    )
    (net (code "379") (name "unconnected-(SV4S-S-Pad26)") (class "Default")
      (node (ref "SV4") (pin "26") (pinfunction "S_26") (pintype "passive"))
    )
    (net (code "380") (name "unconnected-(SV4T-S-Pad27)") (class "Default")
      (node (ref "SV4") (pin "27") (pinfunction "S_27") (pintype "passive"))
    )
    (net (code "381") (name "unconnected-(SV4U-S-Pad28)") (class "Default")
      (node (ref "SV4") (pin "28") (pinfunction "S_28") (pintype "passive"))
    )
    (net (code "382") (name "unconnected-(SV4V-S-Pad29)") (class "Default")
      (node (ref "SV4") (pin "29") (pinfunction "S_29") (pintype "passive"))
    )
    (net (code "383") (name "unconnected-(SV4X-S-Pad30)") (class "Default")
      (node (ref "SV4") (pin "30") (pinfunction "S_30") (pintype "passive"))
    )
    (net (code "384") (name "unconnected-(SV4Y-S-Pad31)") (class "Default")
      (node (ref "SV4") (pin "31") (pinfunction "S_31") (pintype "passive"))
    )
    (net (code "385") (name "unconnected-(SV4Z-S-Pad32)") (class "Default")
      (node (ref "SV4") (pin "32") (pinfunction "S_32") (pintype "passive"))
    )
    (net (code "386") (name "unconnected-(U3A-B1-Pad18)") (class "Default")
      (node (ref "U3") (pin "18") (pinfunction "B1_18") (pintype "bidirectional"))
    )
    (net (code "387") (name "unconnected-(U3A-B2-Pad17)") (class "Default")
      (node (ref "U3") (pin "17") (pinfunction "B2_17") (pintype "bidirectional"))
    )
    (net (code "388") (name "unconnected-(U3A-B4-Pad15)") (class "Default")
      (node (ref "U3") (pin "15") (pinfunction "B4_15") (pintype "bidirectional"))
    )
    (net (code "389") (name "unconnected-(U3A-B6-Pad13)") (class "Default")
      (node (ref "U3") (pin "13") (pinfunction "B6_13") (pintype "bidirectional"))
    )
    (net (code "390") (name "unconnected-(U6E-O-Pad10)") (class "Default")
      (node (ref "U6") (pin "10") (pinfunction "O_10") (pintype "output"))
    )
    (net (code "391") (name "unconnected-(U6F-O-Pad12)") (class "Default")
      (node (ref "U6") (pin "12") (pinfunction "O_12") (pintype "output"))
    )
    (net (code "392") (name "unconnected-(U7B-Q-Pad9)") (class "Default")
      (node (ref "U7") (pin "9") (pinfunction "Q_9") (pintype "output"))
    )
    (net (code "393") (name "unconnected-(U7B-~{Q}-Pad8)") (class "Default")
      (node (ref "U7") (pin "8") (pinfunction "~{Q}_8") (pintype "output"))
    )
    (net (code "394") (name "unconnected-(U9A-QA-Pad3)") (class "Default")
      (node (ref "U9") (pin "3") (pinfunction "QA_3") (pintype "output"))
    )
    (net (code "395") (name "unconnected-(U9A-QB-Pad4)") (class "Default")
      (node (ref "U9") (pin "4") (pinfunction "QB_4") (pintype "output"))
    )
    (net (code "396") (name "unconnected-(U9A-QC-Pad5)") (class "Default")
      (node (ref "U9") (pin "5") (pinfunction "QC_5") (pintype "output"))
    )
    (net (code "397") (name "unconnected-(U9B-QA-Pad11)") (class "Default")
      (node (ref "U9") (pin "11") (pinfunction "QA_11") (pintype "output"))
    )
    (net (code "398") (name "unconnected-(U9B-QB-Pad10)") (class "Default")
      (node (ref "U9") (pin "10") (pinfunction "QB_10") (pintype "output"))
    )
    (net (code "399") (name "unconnected-(U9B-QC-Pad9)") (class "Default")
      (node (ref "U9") (pin "9") (pinfunction "QC_9") (pintype "output"))
    )
    (net (code "400") (name "unconnected-(U9B-QD-Pad8)") (class "Default")
      (node (ref "U9") (pin "8") (pinfunction "QD_8") (pintype "output"))
    )
    (net (code "401") (name "unconnected-(U10C-O-Pad8)") (class "Default")
      (node (ref "U10") (pin "8") (pinfunction "O_8") (pintype "output"))
    )
    (net (code "402") (name "unconnected-(U10D-O-Pad11)") (class "Default")
      (node (ref "U10") (pin "11") (pinfunction "O_11") (pintype "output"))
    )
    (net (code "403") (name "unconnected-(U12C-O-Pad8)") (class "Default")
      (node (ref "U12") (pin "8") (pinfunction "O_8") (pintype "output"))
    )
    (net (code "404") (name "unconnected-(U12D-O-Pad11)") (class "Default")
      (node (ref "U12") (pin "11") (pinfunction "O_11") (pintype "output"))
    )
    (net (code "405") (name "unconnected-(U13A-3Q-Pad17)") (class "Default")
      (node (ref "U13") (pin "17") (pinfunction "3Q_17") (pintype "tri_state"))
    )
    (net (code "406") (name "unconnected-(U13A-4Q-Pad16)") (class "Default")
      (node (ref "U13") (pin "16") (pinfunction "4Q_16") (pintype "tri_state"))
    )
    (net (code "407") (name "unconnected-(U13A-5Q-Pad15)") (class "Default")
      (node (ref "U13") (pin "15") (pinfunction "5Q_15") (pintype "tri_state"))
    )
    (net (code "408") (name "unconnected-(U13A-6Q-Pad14)") (class "Default")
      (node (ref "U13") (pin "14") (pinfunction "6Q_14") (pintype "tri_state"))
    )
    (net (code "409") (name "unconnected-(U13A-7Q-Pad13)") (class "Default")
      (node (ref "U13") (pin "13") (pinfunction "7Q_13") (pintype "tri_state"))
    )
    (net (code "410") (name "unconnected-(U13A-8Q-Pad12)") (class "Default")
      (node (ref "U13") (pin "12") (pinfunction "8Q_12") (pintype "tri_state"))
    )
    (net (code "411") (name "unconnected-(U14A-Y0-Pad15)") (class "Default")
      (node (ref "U14") (pin "15") (pinfunction "Y0_15") (pintype "output"))
    )
    (net (code "412") (name "unconnected-(U14A-Y4-Pad11)") (class "Default")
      (node (ref "U14") (pin "11") (pinfunction "Y4_11") (pintype "output"))
    )
    (net (code "413") (name "unconnected-(U14A-Y5-Pad10)") (class "Default")
      (node (ref "U14") (pin "10") (pinfunction "Y5_10") (pintype "output"))
    )
    (net (code "414") (name "unconnected-(U14A-Y6-Pad9)") (class "Default")
      (node (ref "U14") (pin "9") (pinfunction "Y6_9") (pintype "output"))
    )
    (net (code "415") (name "unconnected-(U14A-Y7-Pad7)") (class "Default")
      (node (ref "U14") (pin "7") (pinfunction "Y7_7") (pintype "output"))
    )
    (net (code "416") (name "unconnected-(U31A-QH*-Pad9)") (class "Default")
      (node (ref "U31") (pin "9") (pinfunction "QH*_9") (pintype "tri_state"))
    )
  )
)
